# Sheet1.net
KiCad netlist of a schematic drawn in Altium Designer
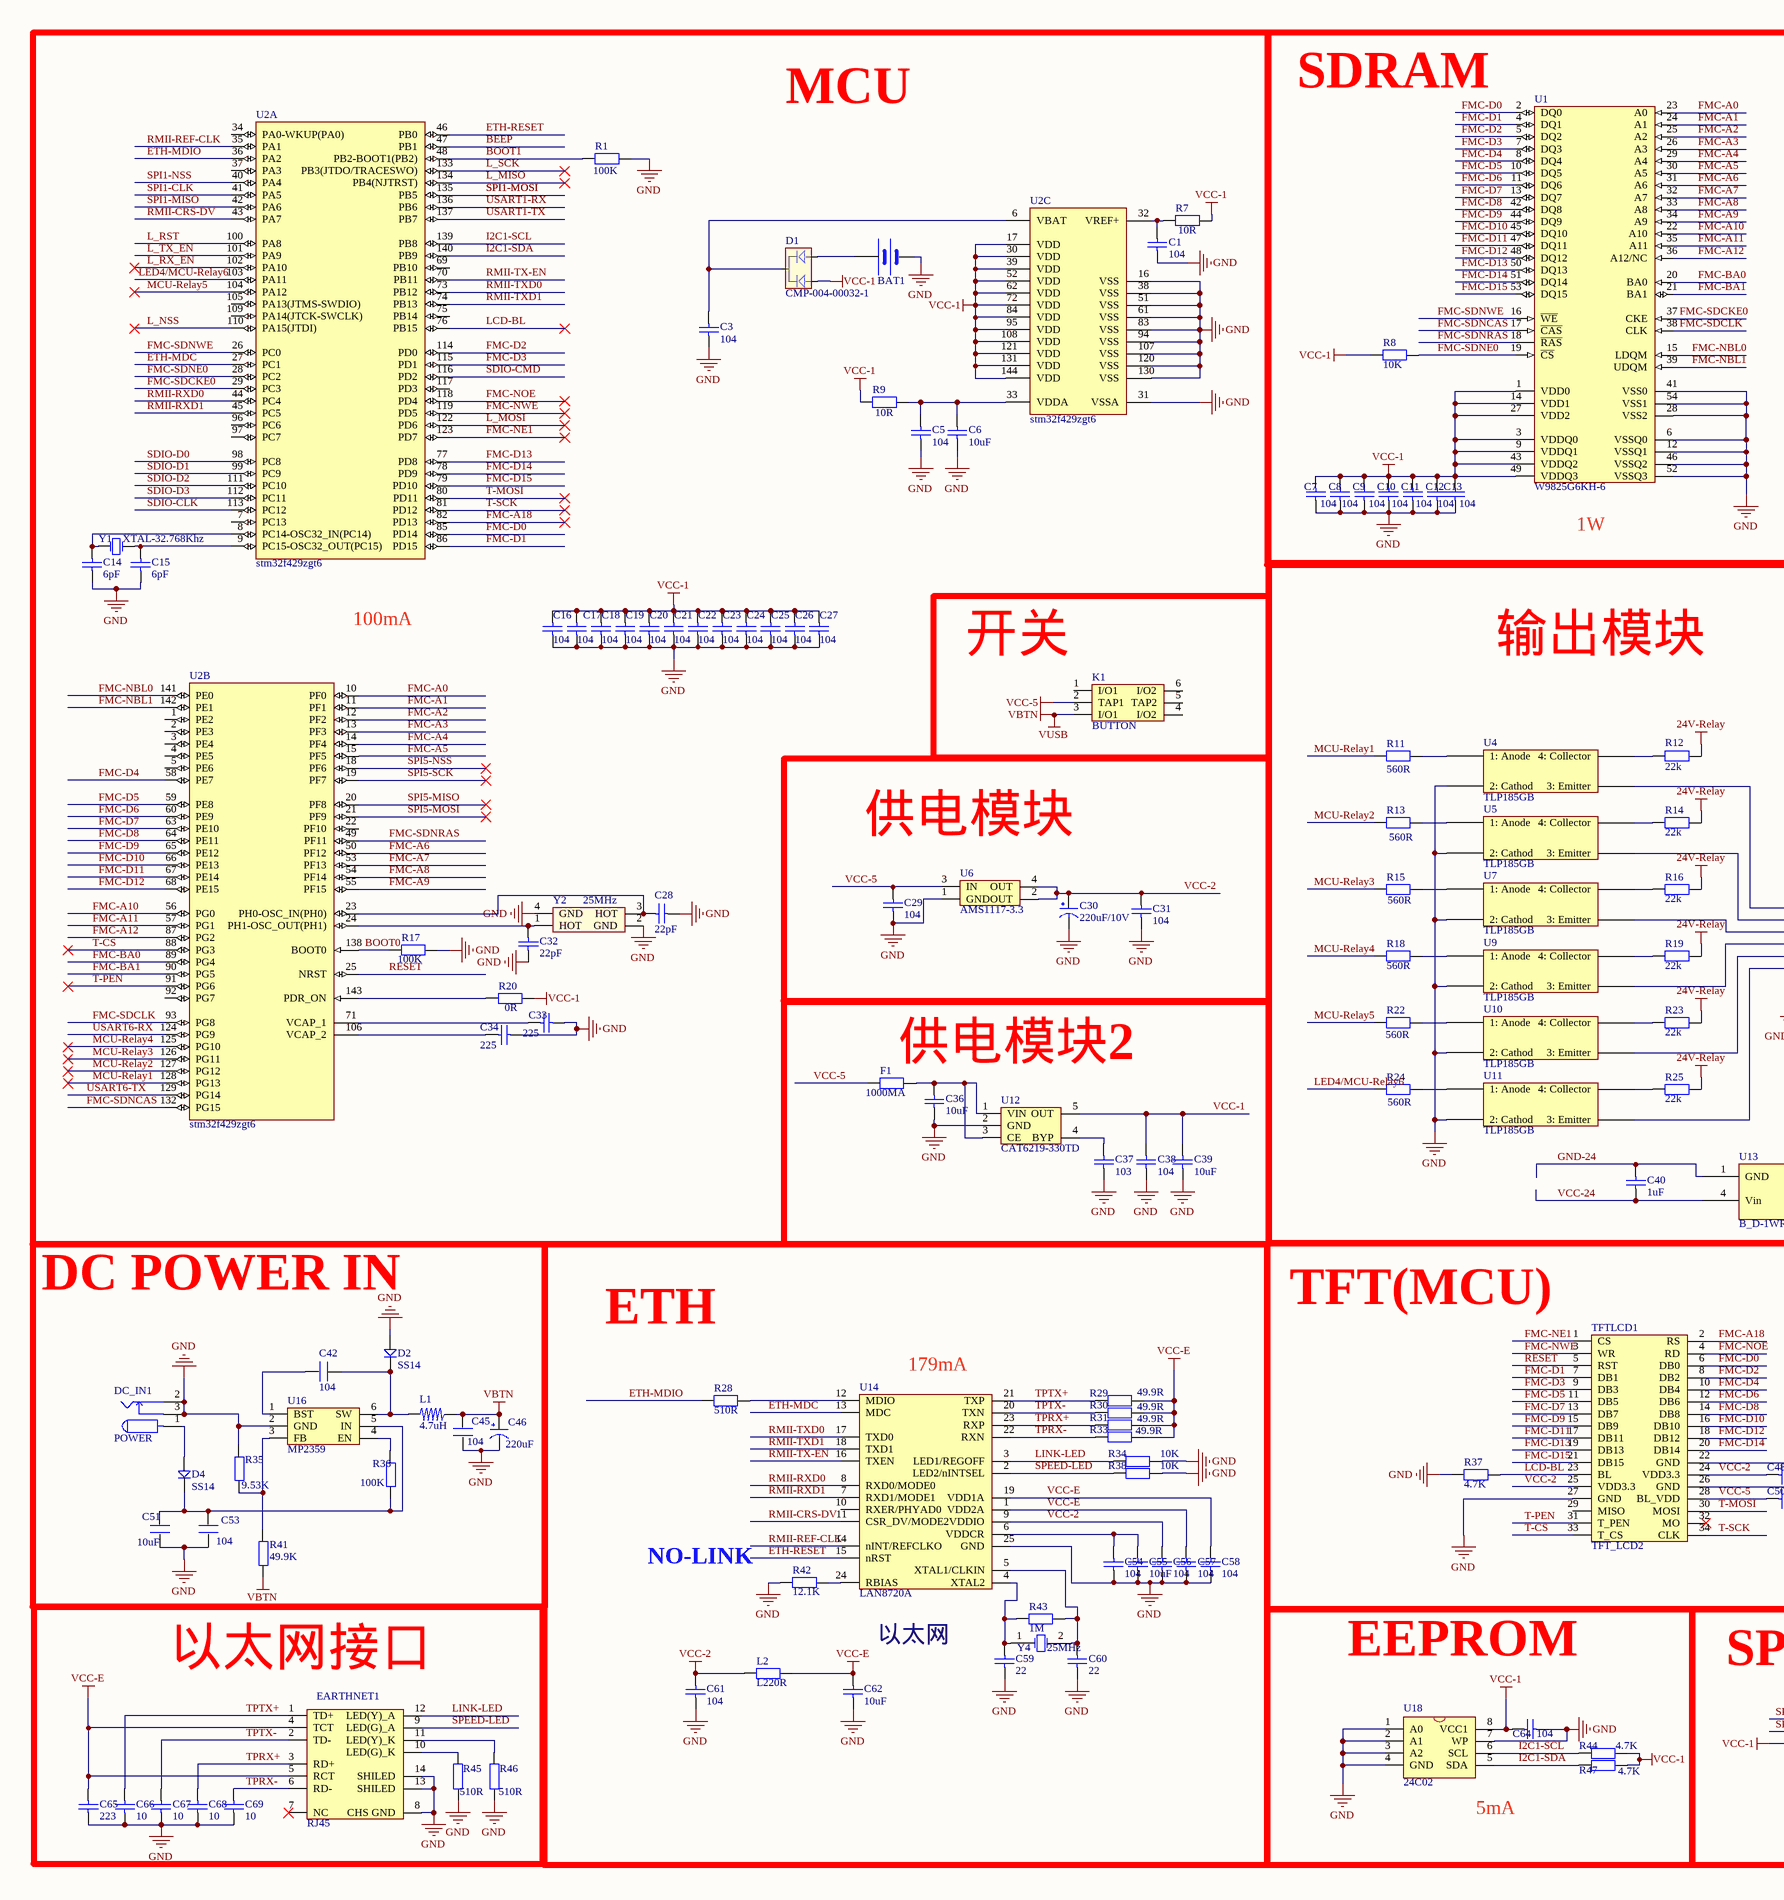
[diagram p0: Sheet1.SchDoc, left]
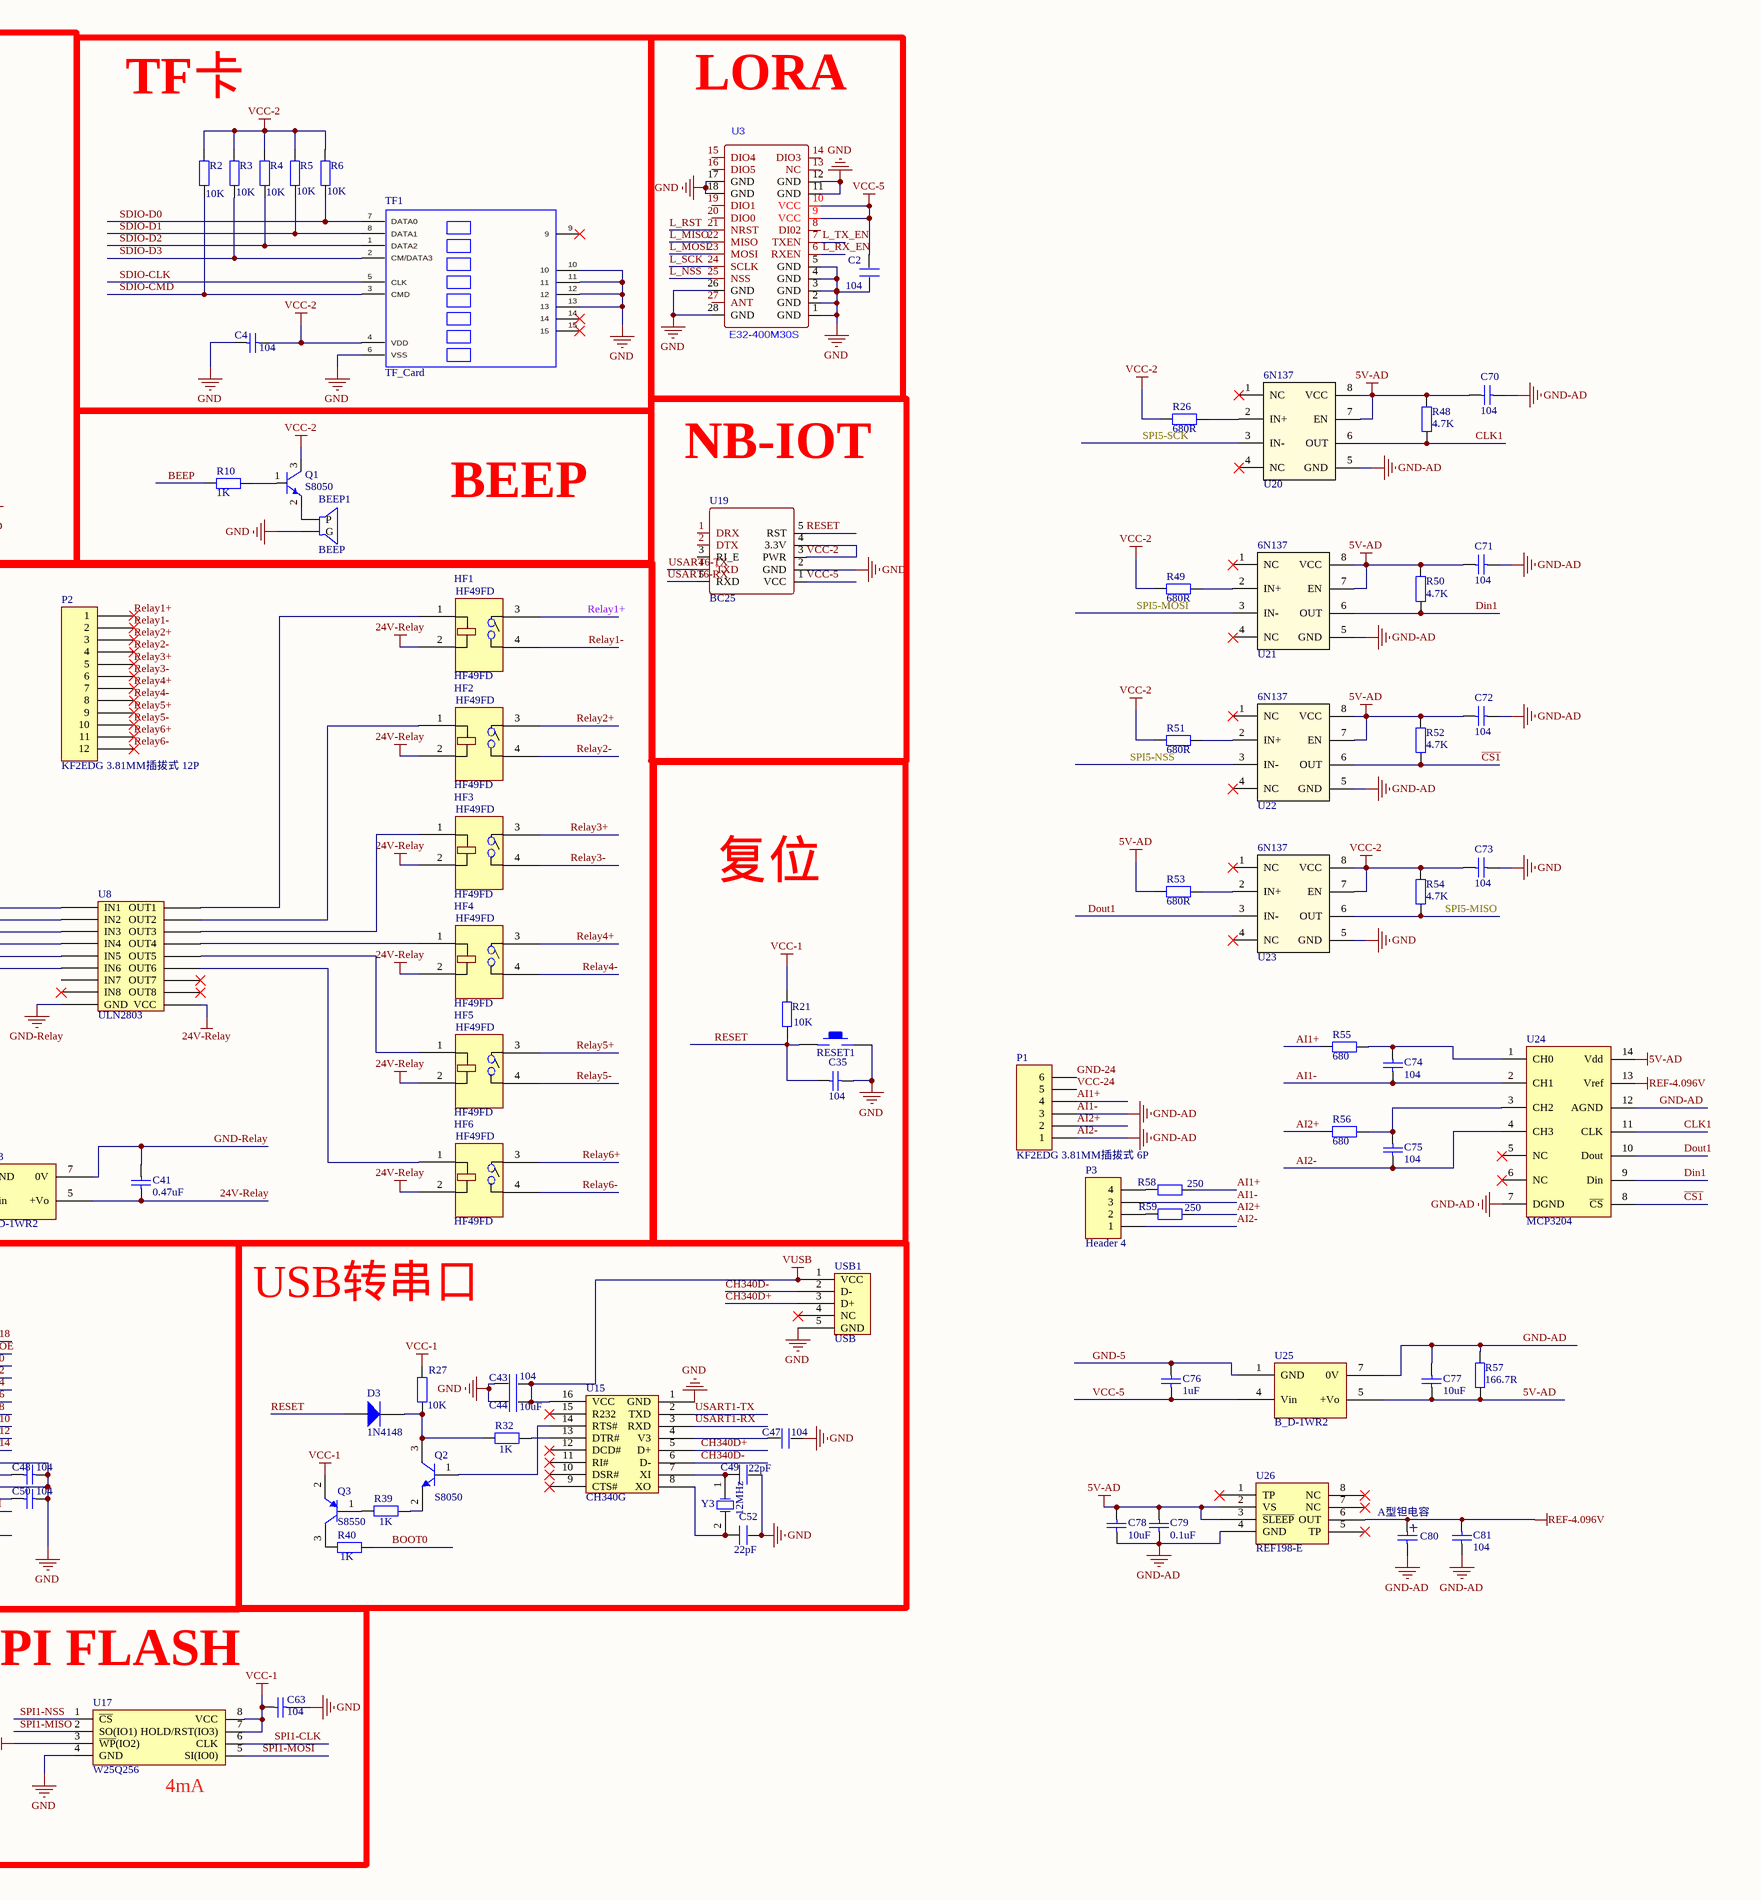
[diagram p1: Sheet1.SchDoc, right]

(export (version "E")
  (design (tool "Eeschema 10.0.6"))
  (components
    (comp (ref "BAT1")
      (value "CMP-00029-00001-1")
      (footprint "BATM")
      (libsource (lib "DigiPCBA Workspace") (part "BAT"))
    )
    (comp (ref "BEEP1")
      (value "BEEP")
      (footprint "BELL-5")
      (libsource (lib "DigiPCBA Workspace") (part "BEEP"))
    )
    (comp (ref "C1")
      (value "104")
      (footprint "LC-0603_C")
      (fields (field (name "Comment") "CAP"))
      (libsource (lib "DigiPCBA Workspace") (part "CAP"))
    )
    (comp (ref "C2") (value "104") (footprint "0603P") (libsource (lib "DigiPCBA Workspace") (part "C")))
    (comp (ref "C3")
      (value "104")
      (footprint "LC-0603_C")
      (fields (field (name "Comment") "CAP"))
      (libsource (lib "DigiPCBA Workspace") (part "CAP"))
    )
    (comp (ref "C4")
      (value "104")
      (footprint "CAP")
      (fields (field (name "Comment") "CMP-001-00083-1"))
      (libsource (lib "DigiPCBA Workspace") (part "CAP"))
    )
    (comp (ref "C5")
      (value "104")
      (footprint "LC-0603_C")
      (fields (field (name "Comment") "CAP"))
      (libsource (lib "DigiPCBA Workspace") (part "CAP"))
    )
    (comp (ref "C6")
      (value "10uF")
      (footprint "LC-0603_C")
      (fields (field (name "Comment") "CMP-001-00083-1"))
      (libsource (lib "DigiPCBA Workspace") (part "CAP"))
    )
    (comp (ref "C7")
      (value "104")
      (footprint "LC-0603_C")
      (fields (field (name "Comment") "CAP"))
      (libsource (lib "DigiPCBA Workspace") (part "CAP"))
    )
    (comp (ref "C8")
      (value "104")
      (footprint "LC-0603_C")
      (fields (field (name "Comment") "CAP"))
      (libsource (lib "DigiPCBA Workspace") (part "CAP"))
    )
    (comp (ref "C9")
      (value "104")
      (footprint "LC-0603_C")
      (fields (field (name "Comment") "CAP"))
      (libsource (lib "DigiPCBA Workspace") (part "CAP"))
    )
    (comp (ref "C10")
      (value "104")
      (footprint "LC-0603_C")
      (fields (field (name "Comment") "CAP"))
      (libsource (lib "DigiPCBA Workspace") (part "CAP"))
    )
    (comp (ref "C11")
      (value "104")
      (footprint "LC-0603_C")
      (fields (field (name "Comment") "CAP"))
      (libsource (lib "DigiPCBA Workspace") (part "CAP"))
    )
    (comp (ref "C12")
      (value "104")
      (footprint "LC-0603_C")
      (fields (field (name "Comment") "CAP"))
      (libsource (lib "DigiPCBA Workspace") (part "CAP"))
    )
    (comp (ref "C13")
      (value "104")
      (footprint "LC-0603_C")
      (fields (field (name "Comment") "CAP"))
      (libsource (lib "DigiPCBA Workspace") (part "CAP"))
    )
    (comp (ref "C14")
      (value "6pF")
      (footprint "LC-0603_C")
      (fields (field (name "Comment") "CMP-001-00083-1"))
      (libsource (lib "DigiPCBA Workspace") (part "CAP"))
    )
    (comp (ref "C15")
      (value "6pF")
      (footprint "LC-0603_C")
      (fields (field (name "Comment") "CMP-001-00083-1"))
      (libsource (lib "DigiPCBA Workspace") (part "CAP"))
    )
    (comp (ref "C16")
      (value "104")
      (footprint "LC-0603_C")
      (fields (field (name "Comment") "CMP-001-00083-1"))
      (libsource (lib "DigiPCBA Workspace") (part "CAP"))
    )
    (comp (ref "C17")
      (value "104")
      (footprint "LC-0603_C")
      (fields (field (name "Comment") "CMP-001-00083-1"))
      (libsource (lib "DigiPCBA Workspace") (part "CAP"))
    )
    (comp (ref "C18")
      (value "104")
      (footprint "LC-0603_C")
      (fields (field (name "Comment") "CAP"))
      (libsource (lib "DigiPCBA Workspace") (part "CAP"))
    )
    (comp (ref "C19")
      (value "104")
      (footprint "LC-0603_C")
      (fields (field (name "Comment") "CAP"))
      (libsource (lib "DigiPCBA Workspace") (part "CAP"))
    )
    (comp (ref "C20")
      (value "104")
      (footprint "LC-0603_C")
      (fields (field (name "Comment") "CAP"))
      (libsource (lib "DigiPCBA Workspace") (part "CAP"))
    )
    (comp (ref "C21")
      (value "104")
      (footprint "LC-0603_C")
      (fields (field (name "Comment") "CAP"))
      (libsource (lib "DigiPCBA Workspace") (part "CAP"))
    )
    (comp (ref "C22")
      (value "104")
      (footprint "LC-0603_C")
      (fields (field (name "Comment") "CAP"))
      (libsource (lib "DigiPCBA Workspace") (part "CAP"))
    )
    (comp (ref "C23")
      (value "104")
      (footprint "LC-0603_C")
      (fields (field (name "Comment") "CAP"))
      (libsource (lib "DigiPCBA Workspace") (part "CMP-001-00083-1"))
    )
    (comp (ref "C24")
      (value "104")
      (footprint "LC-0603_C")
      (libsource (lib "DigiPCBA Workspace") (part "CAP"))
    )
    (comp (ref "C25")
      (value "104")
      (footprint "LC-0603_C")
      (fields (field (name "Comment") "CAP"))
      (libsource (lib "DigiPCBA Workspace") (part "CAP"))
    )
    (comp (ref "C26")
      (value "104")
      (footprint "LC-0603_C")
      (fields (field (name "Comment") "CAP"))
      (libsource (lib "DigiPCBA Workspace") (part "CAP"))
    )
    (comp (ref "C27")
      (value "104")
      (footprint "LC-0603_C")
      (fields (field (name "Comment") "CAP"))
      (libsource (lib "DigiPCBA Workspace") (part "CAP"))
    )
    (comp (ref "C28")
      (value "22pF")
      (footprint "LC-0603_C")
      (fields (field (name "Comment") "CMP-001-00083-1"))
      (libsource (lib "DigiPCBA Workspace") (part "CAP"))
    )
    (comp (ref "C29")
      (value "104")
      (footprint "CAP")
      (fields (field (name "Comment") "CMP-001-00083-1"))
      (libsource (lib "DigiPCBA Workspace") (part "CAP"))
    )
    (comp (ref "C30")
      (value "220uF/10V")
      (footprint "220uF/10V")
      (libsource (lib "DigiPCBA Workspace") (part "CAP贴片电解电容"))
    )
    (comp (ref "C31")
      (value "104")
      (footprint "CAP")
      (fields (field (name "Comment") "CMP-001-00083-1"))
      (libsource (lib "DigiPCBA Workspace") (part "CAP"))
    )
    (comp (ref "C32")
      (value "22pF")
      (footprint "LC-0603_C")
      (fields (field (name "Comment") "CMP-001-00083-1"))
      (libsource (lib "DigiPCBA Workspace") (part "CAP"))
    )
    (comp (ref "C33")
      (value "225")
      (footprint "LC-0603_C")
      (fields (field (name "Comment") "CMP-001-00083-1"))
      (libsource (lib "DigiPCBA Workspace") (part "CAP"))
    )
    (comp (ref "C34")
      (value "225")
      (footprint "LC-0603_C")
      (fields (field (name "Comment") "CMP-001-00083-1"))
      (libsource (lib "DigiPCBA Workspace") (part "CAP"))
    )
    (comp (ref "C35")
      (value "104")
      (footprint "LC-0603_C")
      (fields (field (name "Comment") "CAP"))
      (libsource (lib "DigiPCBA Workspace") (part "CAP"))
    )
    (comp (ref "C36")
      (value "10uF")
      (footprint "LC-0603_C")
      (fields (field (name "Comment") "CMP-001-00083-1"))
      (libsource (lib "DigiPCBA Workspace") (part "CAP"))
    )
    (comp (ref "C37")
      (value "103")
      (footprint "CAP")
      (fields (field (name "Comment") "CMP-001-00083-1"))
      (libsource (lib "DigiPCBA Workspace") (part "CAP"))
    )
    (comp (ref "C38")
      (value "104")
      (footprint "CAP")
      (fields (field (name "Comment") "CMP-001-00083-1"))
      (libsource (lib "DigiPCBA Workspace") (part "CAP"))
    )
    (comp (ref "C39")
      (value "10uF")
      (footprint "LC-0603_C")
      (fields (field (name "Comment") "CMP-001-00083-1"))
      (libsource (lib "DigiPCBA Workspace") (part "CAP"))
    )
    (comp (ref "C40")
      (value "1uF")
      (footprint "CAP")
      (fields (field (name "Comment") "CMP-001-00083-1"))
      (libsource (lib "DigiPCBA Workspace") (part "CAP"))
    )
    (comp (ref "C41")
      (value "0.47uF")
      (footprint "CAP")
      (fields (field (name "Comment") "CMP-001-00083-1"))
      (libsource (lib "DigiPCBA Workspace") (part "CAP"))
    )
    (comp (ref "C42") (value "104") (footprint "0603P") (libsource (lib "DigiPCBA Workspace") (part "C")))
    (comp (ref "C43") (value "104") (footprint "0603P") (libsource (lib "DigiPCBA Workspace") (part "C")))
    (comp (ref "C44") (value "10uF") (footprint "0603P") (libsource (lib "DigiPCBA Workspace") (part "C")))
    (comp (ref "C45") (value "104") (footprint "0603P") (libsource (lib "DigiPCBA Workspace") (part "C")))
    (comp (ref "C46") (value "220uF") (footprint "CC6.56.5") (libsource (lib "") (part "CAP_1")))
    (comp (ref "C47") (value "104") (footprint "0603P") (libsource (lib "DigiPCBA Workspace") (part "C")))
    (comp (ref "C48")
      (value "104")
      (footprint "CAP")
      (fields (field (name "Comment") "CMP-001-00083-1"))
      (libsource (lib "DigiPCBA Workspace") (part "CAP"))
    )
    (comp (ref "C49") (value "22pF") (footprint "0603P") (libsource (lib "DigiPCBA Workspace") (part "C")))
    (comp (ref "C50")
      (value "104")
      (footprint "CAP")
      (fields (field (name "Comment") "CMP-001-00083-1"))
      (libsource (lib "DigiPCBA Workspace") (part "CAP"))
    )
    (comp (ref "C51") (value "10uF") (footprint "0603P") (libsource (lib "DigiPCBA Workspace") (part "C")))
    (comp (ref "C52") (value "22pF") (footprint "0603P") (libsource (lib "DigiPCBA Workspace") (part "C")))
    (comp (ref "C53") (value "104") (footprint "0603P") (libsource (lib "DigiPCBA Workspace") (part "C")))
    (comp (ref "C54")
      (value "104")
      (footprint "LC-0603_C")
      (fields (field (name "Comment") "CAP"))
      (libsource (lib "DigiPCBA Workspace") (part "CAP"))
    )
    (comp (ref "C55")
      (value "10uF")
      (footprint "LC-0603_C")
      (fields (field (name "Comment") "CMP-001-00083-1"))
      (libsource (lib "DigiPCBA Workspace") (part "CAP"))
    )
    (comp (ref "C56")
      (value "104")
      (footprint "LC-0603_C")
      (fields (field (name "Comment") "CAP"))
      (libsource (lib "DigiPCBA Workspace") (part "CAP"))
    )
    (comp (ref "C57")
      (value "104")
      (footprint "LC-0603_C")
      (fields (field (name "Comment") "CAP"))
      (libsource (lib "DigiPCBA Workspace") (part "CAP"))
    )
    (comp (ref "C58")
      (value "104")
      (footprint "LC-0603_C")
      (fields (field (name "Comment") "CAP"))
      (libsource (lib "DigiPCBA Workspace") (part "CAP"))
    )
    (comp (ref "C59")
      (value "22")
      (footprint "LC-0603_C")
      (fields (field (name "Comment") "CMP-001-00083-1"))
      (libsource (lib "DigiPCBA Workspace") (part "CAP"))
    )
    (comp (ref "C60")
      (value "22")
      (footprint "LC-0603_C")
      (fields (field (name "Comment") "CMP-001-00083-1"))
      (libsource (lib "DigiPCBA Workspace") (part "CAP"))
    )
    (comp (ref "C61")
      (value "104")
      (footprint "CAP")
      (fields (field (name "Comment") "CMP-001-00083-1"))
      (libsource (lib "DigiPCBA Workspace") (part "CAP"))
    )
    (comp (ref "C62")
      (value "10uF")
      (footprint "LC-0603_C")
      (fields (field (name "Comment") "CMP-001-00083-1"))
      (libsource (lib "DigiPCBA Workspace") (part "CAP"))
    )
    (comp (ref "C63")
      (value "104")
      (footprint "CAP")
      (fields (field (name "Comment") "CMP-001-00083-1"))
      (libsource (lib "DigiPCBA Workspace") (part "CAP"))
    )
    (comp (ref "C64")
      (value "104")
      (footprint "CAP")
      (fields (field (name "Comment") "CMP-001-00083-1"))
      (libsource (lib "DigiPCBA Workspace") (part "CAP"))
    )
    (comp (ref "C65")
      (value "223")
      (footprint "CAP")
      (fields (field (name "Comment") "CMP-001-00083-1"))
      (libsource (lib "DigiPCBA Workspace") (part "CAP"))
    )
    (comp (ref "C66")
      (value "10")
      (footprint "CAP")
      (fields (field (name "Comment") "CMP-001-00083-1"))
      (libsource (lib "DigiPCBA Workspace") (part "CAP"))
    )
    (comp (ref "C67")
      (value "10")
      (footprint "CAP")
      (fields (field (name "Comment") "CMP-001-00083-1"))
      (libsource (lib "DigiPCBA Workspace") (part "CAP"))
    )
    (comp (ref "C68")
      (value "10")
      (footprint "CAP")
      (fields (field (name "Comment") "CMP-001-00083-1"))
      (libsource (lib "DigiPCBA Workspace") (part "CAP"))
    )
    (comp (ref "C69")
      (value "10")
      (footprint "CAP")
      (fields (field (name "Comment") "CMP-001-00083-1"))
      (libsource (lib "DigiPCBA Workspace") (part "CAP"))
    )
    (comp (ref "C70")
      (value "104")
      (footprint "CAP")
      (fields (field (name "Comment") "CAP"))
      (libsource (lib "Integrated_Library3") (part "CAP"))
    )
    (comp (ref "C71")
      (value "104")
      (footprint "CAP")
      (fields (field (name "Comment") "CAP"))
      (libsource (lib "Integrated_Library3") (part "CAP"))
    )
    (comp (ref "C72")
      (value "104")
      (footprint "CAP")
      (fields (field (name "Comment") "CAP"))
      (libsource (lib "Integrated_Library3") (part "CAP"))
    )
    (comp (ref "C73")
      (value "104")
      (footprint "CAP")
      (fields (field (name "Comment") "CAP"))
      (libsource (lib "Integrated_Library3") (part "CAP"))
    )
    (comp (ref "C74")
      (value "104")
      (footprint "CAP")
      (fields (field (name "Comment") "CAP"))
      (libsource (lib "Integrated_Library3") (part "CAP"))
    )
    (comp (ref "C75")
      (value "104")
      (footprint "CAP")
      (fields (field (name "Comment") "CAP"))
      (libsource (lib "Integrated_Library3") (part "CAP"))
    )
    (comp (ref "C76")
      (value "1uF")
      (footprint "CAP")
      (fields (field (name "Comment") "CMP-001-00083-1"))
      (libsource (lib "DigiPCBA Workspace") (part "CAP"))
    )
    (comp (ref "C77")
      (value "10uF")
      (footprint "CAP")
      (fields (field (name "Comment") "CMP-001-00083-1"))
      (libsource (lib "DigiPCBA Workspace") (part "CAP"))
    )
    (comp (ref "C78")
      (value "10uF")
      (footprint "CAP")
      (fields (field (name "Comment") "CAP"))
      (libsource (lib "Integrated_Library3") (part "CAP"))
    )
    (comp (ref "C79")
      (value "0.1uF")
      (footprint "CAP")
      (fields (field (name "Comment") "CAP"))
      (libsource (lib "Integrated_Library3") (part "CAP"))
    )
    (comp (ref "C80")
      (value "A型钽电容")
      (footprint "A型贴片钽电容")
      (libsource (lib "DigiPCBA Workspace") (part "A型钽电容"))
    )
    (comp (ref "C81")
      (value "104")
      (footprint "CAP")
      (fields (field (name "Comment") "CAP"))
      (libsource (lib "Integrated_Library3") (part "CAP"))
    )
    (comp (ref "D1")
      (value "CMP-004-00032-1")
      (footprint "SOT-23")
      (description "双肖特基二极管")
      (libsource (lib "DigiPCBA Workspace") (part "BAT54C"))
    )
    (comp (ref "D2")
      (value "SS14")
      (footprint "DIODE_3*5.3")
      (libsource (lib "DigiPCBA Workspace") (part "D"))
    )
    (comp (ref "D3")
      (value "1N4148")
      (footprint "3.2X1.6X1.1")
      (fields (field (name "SOURCE") "主控芯片.SCHLIB"))
      (libsource (lib "DigiPCBA Workspace") (part "DIODE"))
    )
    (comp (ref "D4")
      (value "SS14")
      (footprint "DIODE_3*5.3")
      (libsource (lib "DigiPCBA Workspace") (part "D"))
    )
    (comp (ref "DC_IN1")
      (value "POWER")
      (footprint "DC10B")
      (libsource (lib "DigiPCBA Workspace") (part "POW"))
    )
    (comp (ref "EARTHNET1")
      (value "RJ45")
      (footprint "HR911105A")
      (libsource (lib "DigiPCBA Workspace") (part "HR911105"))
    )
    (comp (ref "F1")
      (value "1000MA")
      (footprint "RES")
      (fields (field (name "Comment") "CMP-009-00177-1"))
      (libsource (lib "") (part "RES_2"))
    )
    (comp (ref "HF1")
      (value "HF49FD")
      (footprint "HF49FDXXX_1HX1")
      (fields (field (name "SOURCE") "电源模块.SCHLIB"))
      (libsource (lib "DigiPCBA Workspace") (part "HF49FD"))
    )
    (comp (ref "HF2")
      (value "HF49FD")
      (footprint "HF49FDXXX_1HX1")
      (fields (field (name "SOURCE") "电源模块.SCHLIB"))
      (libsource (lib "DigiPCBA Workspace") (part "HF49FD"))
    )
    (comp (ref "HF3")
      (value "HF49FD")
      (footprint "HF49FDXXX_1HX1")
      (fields (field (name "SOURCE") "电源模块.SCHLIB"))
      (libsource (lib "DigiPCBA Workspace") (part "HF49FD"))
    )
    (comp (ref "HF4")
      (value "HF49FD")
      (footprint "HF49FDXXX_1HX1")
      (fields (field (name "SOURCE") "电源模块.SCHLIB"))
      (libsource (lib "DigiPCBA Workspace") (part "HF49FD"))
    )
    (comp (ref "HF5")
      (value "HF49FD")
      (footprint "HF49FDXXX_1HX1")
      (fields (field (name "SOURCE") "电源模块.SCHLIB"))
      (libsource (lib "DigiPCBA Workspace") (part "HF49FD"))
    )
    (comp (ref "HF6")
      (value "HF49FD")
      (footprint "HF49FDXXX_1HX1")
      (fields (field (name "SOURCE") "电源模块.SCHLIB"))
      (libsource (lib "DigiPCBA Workspace") (part "HF49FD"))
    )
    (comp (ref "K1")
      (value "BUTTON")
      (footprint "BTN8.5*8.5")
      (libsource (lib "DigiPCBA Workspace") (part "BUTTON"))
    )
    (comp (ref "L1")
      (value "4.7uH")
      (footprint "L_SOP74")
      (libsource (lib "DigiPCBA Workspace") (part "L_SOP"))
    )
    (comp (ref "L2") (value "L220R") (footprint "RES") (libsource (lib "") (part "RES_2")))
    (comp (ref "P1")
      (value "KF2EDG 3.81MM插拔式 6P")
      (footprint "KF2EDG 3.81MM拔插")
      (description "Header, 6-Pin")
      (fields (field (name "PUBLISHER") "Altium Limited"))
      (libsource (lib "电源模块") (part "Header 6"))
    )
    (comp (ref "P2")
      (value "KF2EDG 3.81MM插拔式 12P")
      (footprint "KF2EDG 3.81mm插拔式")
      (fields (field (name "SOURCE") "电源模块.SCHLIB"))
      (libsource (lib "DigiPCBA Workspace") (part "KF2EDG 3.81MM插拔式 12P"))
    )
    (comp (ref "P3")
      (value "Header 4")
      (footprint "HDR1X4")
      (description "Header, 4-Pin")
      (fields (field (name "PUBLISHER") "Altium Limited"))
      (libsource (lib "DigiPCBA Workspace") (part "Header 4"))
    )
    (comp (ref "Q1")
      (value "S8050")
      (footprint "NPN/PNP")
      (description "NPN")
      (libsource (lib "DigiPCBA Workspace") (part "NPN"))
    )
    (comp (ref "Q2")
      (value "S8050")
      (footprint "SOT-23_N")
      (fields (field (name "SOURCE") "主控芯片.SCHLIB"))
      (libsource (lib "DigiPCBA Workspace") (part "QNPN"))
    )
    (comp (ref "Q3")
      (value "S8550")
      (footprint "SOT-23B_N")
      (fields (field (name "SOURCE") "主控芯片.SCHLIB"))
      (libsource (lib "DigiPCBA Workspace") (part "QPNP"))
    )
    (comp (ref "R1")
      (value "100K")
      (footprint "LC-0603_R")
      (fields (field (name "Comment") "CMP-009-00177-1"))
      (libsource (lib "DigiPCBA Workspace") (part "RES"))
    )
    (comp (ref "R2") (value "10K") (footprint "RES") (libsource (lib "") (part "RES_1")))
    (comp (ref "R3") (value "10K") (footprint "RES") (libsource (lib "") (part "RES_1")))
    (comp (ref "R4") (value "10K") (footprint "RES") (libsource (lib "") (part "RES_1")))
    (comp (ref "R5") (value "10K") (footprint "RES") (libsource (lib "") (part "RES_1")))
    (comp (ref "R6") (value "10K") (footprint "RES") (libsource (lib "") (part "RES_1")))
    (comp (ref "R7")
      (value "10R")
      (footprint "LC-0603_R")
      (fields (field (name "Comment") "CMP-009-00177-1"))
      (libsource (lib "") (part "RES_2"))
    )
    (comp (ref "R8") (value "10K") (footprint "LC-0603_R") (libsource (lib "") (part "RES_2")))
    (comp (ref "R9")
      (value "10R")
      (footprint "LC-0603_R")
      (fields (field (name "Comment") "CMP-009-00177-1"))
      (libsource (lib "") (part "RES_2"))
    )
    (comp (ref "R10") (value "1K") (footprint "RES") (libsource (lib "") (part "RES_2")))
    (comp (ref "R11")
      (value "560R")
      (footprint "RES")
      (fields (field (name "Comment") "RES") (field (name "SOURCE") "电源模块.SCHLIB"))
      (libsource (lib "DigiPCBA Workspace") (part "RES_1"))
    )
    (comp (ref "R12")
      (value "22k")
      (footprint "RES")
      (fields (field (name "Comment") "CMP-009-00180-1") (field (name "SOURCE") "电源模块.SCHLIB"))
      (libsource (lib "DigiPCBA Workspace") (part "RES_1"))
    )
    (comp (ref "R13")
      (value "560R")
      (footprint "RES")
      (fields (field (name "Comment") "RES") (field (name "SOURCE") "电源模块.SCHLIB"))
      (libsource (lib "DigiPCBA Workspace") (part "RES_1"))
    )
    (comp (ref "R14")
      (value "22k")
      (footprint "RES")
      (fields (field (name "Comment") "CMP-009-00180-1") (field (name "SOURCE") "电源模块.SCHLIB"))
      (libsource (lib "DigiPCBA Workspace") (part "RES_1"))
    )
    (comp (ref "R15")
      (value "560R")
      (footprint "RES")
      (fields (field (name "Comment") "RES") (field (name "SOURCE") "电源模块.SCHLIB"))
      (libsource (lib "DigiPCBA Workspace") (part "RES_1"))
    )
    (comp (ref "R16")
      (value "22k")
      (footprint "RES")
      (fields (field (name "Comment") "CMP-009-00180-1") (field (name "SOURCE") "电源模块.SCHLIB"))
      (libsource (lib "DigiPCBA Workspace") (part "RES_1"))
    )
    (comp (ref "R17")
      (value "100K")
      (footprint "LC-0603_R")
      (fields (field (name "Comment") "CMP-009-00177-1"))
      (libsource (lib "") (part "RES_2"))
    )
    (comp (ref "R18")
      (value "560R")
      (footprint "RES")
      (fields (field (name "Comment") "RES") (field (name "SOURCE") "电源模块.SCHLIB"))
      (libsource (lib "DigiPCBA Workspace") (part "RES_1"))
    )
    (comp (ref "R19")
      (value "22k")
      (footprint "RES")
      (fields (field (name "Comment") "CMP-009-00180-1") (field (name "SOURCE") "电源模块.SCHLIB"))
      (libsource (lib "DigiPCBA Workspace") (part "RES_1"))
    )
    (comp (ref "R20")
      (value "0R")
      (footprint "RES")
      (fields (field (name "Comment") "CMP-009-00177-1"))
      (libsource (lib "DigiPCBA Workspace") (part "RES"))
    )
    (comp (ref "R21") (value "10K") (footprint "LC-0603_R") (libsource (lib "") (part "RES_1")))
    (comp (ref "R22")
      (value "560R")
      (footprint "RES")
      (fields (field (name "Comment") "RES") (field (name "SOURCE") "电源模块.SCHLIB"))
      (libsource (lib "DigiPCBA Workspace") (part "RES_1"))
    )
    (comp (ref "R23")
      (value "22k")
      (footprint "RES")
      (fields (field (name "Comment") "CMP-009-00180-1") (field (name "SOURCE") "电源模块.SCHLIB"))
      (libsource (lib "DigiPCBA Workspace") (part "RES_1"))
    )
    (comp (ref "R24")
      (value "560R")
      (footprint "RES")
      (fields (field (name "Comment") "RES") (field (name "SOURCE") "电源模块.SCHLIB"))
      (libsource (lib "DigiPCBA Workspace") (part "RES_1"))
    )
    (comp (ref "R25")
      (value "22k")
      (footprint "RES")
      (fields (field (name "Comment") "CMP-009-00180-1") (field (name "SOURCE") "电源模块.SCHLIB"))
      (libsource (lib "DigiPCBA Workspace") (part "RES_1"))
    )
    (comp (ref "R26")
      (value "680R")
      (footprint "RES")
      (fields (field (name "Comment") "RES"))
      (libsource (lib "") (part "RES_1"))
    )
    (comp (ref "R27")
      (value "10K")
      (footprint "0805R")
      (fields (field (name "SOURCE") "主控芯片.SCHLIB"))
      (libsource (lib "") (part "RES_4"))
    )
    (comp (ref "R28") (value "510R") (footprint "LC-0603_R") (libsource (lib "") (part "RES_2")))
    (comp (ref "R29") (value "49.9R") (footprint "LC-0603_R") (libsource (lib "") (part "RES_2")))
    (comp (ref "R30") (value "49.9R") (footprint "LC-0603_R") (libsource (lib "") (part "RES_2")))
    (comp (ref "R31") (value "49.9R") (footprint "LC-0603_R") (libsource (lib "") (part "RES_2")))
    (comp (ref "R32")
      (value "1K")
      (footprint "0805R")
      (fields (field (name "SOURCE") "主控芯片.SCHLIB"))
      (libsource (lib "") (part "RES_3"))
    )
    (comp (ref "R33") (value "49.9R") (footprint "LC-0603_R") (libsource (lib "") (part "RES_2")))
    (comp (ref "R34") (value "10K") (footprint "LC-0603_R") (libsource (lib "") (part "RES_2")))
    (comp (ref "R35") (value "9.53K") (footprint "0603P") (libsource (lib "DigiPCBA Workspace") (part "R")))
    (comp (ref "R36") (value "100K") (footprint "0603P") (libsource (lib "DigiPCBA Workspace") (part "R")))
    (comp (ref "R37")
      (value "4.7K")
      (footprint "RES")
      (fields (field (name "Comment") "CMP-009-00180-1") (field (name "SOURCE") "电源模块.SCHLIB"))
      (libsource (lib "DigiPCBA Workspace") (part "RES_1"))
    )
    (comp (ref "R38") (value "10K") (footprint "LC-0603_R") (libsource (lib "") (part "RES_2")))
    (comp (ref "R39")
      (value "1K")
      (footprint "0805R")
      (fields (field (name "SOURCE") "主控芯片.SCHLIB"))
      (libsource (lib "") (part "RES_3"))
    )
    (comp (ref "R40")
      (value "1K")
      (footprint "0805R")
      (fields (field (name "SOURCE") "主控芯片.SCHLIB"))
      (libsource (lib "") (part "RES_5"))
    )
    (comp (ref "R41") (value "49.9K") (footprint "0603P") (libsource (lib "DigiPCBA Workspace") (part "R")))
    (comp (ref "R42") (value "12.1K") (footprint "LC-0603_R") (libsource (lib "") (part "RES_2")))
    (comp (ref "R43") (value "1M") (footprint "LC-0603_R") (libsource (lib "") (part "RES_2")))
    (comp (ref "R44")
      (value "4.7K")
      (footprint "RES")
      (fields (field (name "Comment") "CMP-009-00180-1") (field (name "SOURCE") "电源模块.SCHLIB"))
      (libsource (lib "DigiPCBA Workspace") (part "RES_1"))
    )
    (comp (ref "R45") (value "510R") (footprint "RES") (libsource (lib "") (part "RES_1")))
    (comp (ref "R46") (value "510R") (footprint "RES") (libsource (lib "") (part "RES_1")))
    (comp (ref "R47") (value "4.7K") (footprint "RES") (libsource (lib "") (part "RES_2")))
    (comp (ref "R48")
      (value "4.7K")
      (footprint "RES")
      (fields (field (name "Comment") "RES"))
      (libsource (lib "Integrated_Library3") (part "RES"))
    )
    (comp (ref "R49")
      (value "680R")
      (footprint "RES")
      (fields (field (name "Comment") "RES"))
      (libsource (lib "") (part "RES_1"))
    )
    (comp (ref "R50")
      (value "4.7K")
      (footprint "RES")
      (fields (field (name "Comment") "RES"))
      (libsource (lib "Integrated_Library3") (part "RES"))
    )
    (comp (ref "R51")
      (value "680R")
      (footprint "RES")
      (fields (field (name "Comment") "RES"))
      (libsource (lib "") (part "RES_1"))
    )
    (comp (ref "R52")
      (value "4.7K")
      (footprint "RES")
      (fields (field (name "Comment") "RES"))
      (libsource (lib "Integrated_Library3") (part "RES"))
    )
    (comp (ref "R53")
      (value "680R")
      (footprint "RES")
      (fields (field (name "Comment") "RES"))
      (libsource (lib "") (part "RES_1"))
    )
    (comp (ref "R54")
      (value "4.7K")
      (footprint "RES")
      (fields (field (name "Comment") "RES"))
      (libsource (lib "Integrated_Library3") (part "RES"))
    )
    (comp (ref "R55")
      (value "680")
      (footprint "RES")
      (fields (field (name "Comment") "RES"))
      (libsource (lib "") (part "RES_1"))
    )
    (comp (ref "R56")
      (value "680")
      (footprint "RES")
      (fields (field (name "Comment") "RES"))
      (libsource (lib "") (part "RES_1"))
    )
    (comp (ref "R57")
      (value "166.7R")
      (footprint "1206_R")
      (fields (field (name "Comment") "CMP-009-00180-1") (field (name "SOURCE") "电源模块.SCHLIB"))
      (libsource (lib "") (part "RES_1_1"))
    )
    (comp (ref "R58")
      (value "250")
      (footprint "1206_R")
      (fields (field (name "Comment") "CMP-009-00180-1") (field (name "SOURCE") "电源模块.SCHLIB"))
      (libsource (lib "") (part "RES_1_2"))
    )
    (comp (ref "R59")
      (value "250")
      (footprint "1206_R")
      (fields (field (name "Comment") "CMP-009-00180-1") (field (name "SOURCE") "电源模块.SCHLIB"))
      (libsource (lib "") (part "RES_1_2"))
    )
    (comp (ref "RESET1")
      (value "CMP-012-000013-1")
      (footprint "KEY_M")
      (libsource (lib "DigiPCBA Workspace") (part "KEY_M"))
    )
    (comp (ref "TF1")
      (value "TF_Card")
      (footprint "TF_CARD")
      (libsource (lib "DigiPCBA Workspace") (part "TF_Card"))
    )
    (comp (ref "TFTLCD1")
      (value "TFT_LCD2")
      (footprint "DB2*17-3.5")
      (fields (field (name "SOURCE") "显示模块.SCHLIB"))
      (libsource (lib "DigiPCBA Workspace") (part "TFT_LCD2"))
    )
    (comp (ref "U1")
      (value "W9825G6KH-6")
      (footprint "TSOP54")
      (description "32MB SDRAM")
      (libsource (lib "DigiPCBA Workspace") (part "IS42S16160B"))
    )
    (comp (ref "U2")
      (value "stm32f429zgt6")
      (footprint "STM-LQFP144_N")
      (fields (field (name "MANUFACTURER") "STMicroelectronics") (field (name "PARTNUMBER") "STM32F429ZGT6"))
      (libsource (lib "DigiPCBA Workspace") (part "STM32F429ZGT6"))
    )
    (comp (ref "U3")
      (value "E32-400M30S")
      (footprint "WIRELM-SMD_E32-400M30S")
      (libsource (lib "DigiPCBA Workspace") (part "E32-400M30S"))
    )
    (comp (ref "U4")
      (value "TLP185GB")
      (footprint "TLP185GB")
      (fields (field (name "SOURCE") "电源模块.SCHLIB"))
      (libsource (lib "DigiPCBA Workspace") (part "TLP185GB"))
    )
    (comp (ref "U5")
      (value "TLP185GB")
      (footprint "TLP185GB")
      (fields (field (name "SOURCE") "电源模块.SCHLIB"))
      (libsource (lib "DigiPCBA Workspace") (part "TLP185GB"))
    )
    (comp (ref "U6")
      (value "AMS1117-3.3")
      (footprint "AMS1117")
      (libsource (lib "DigiPCBA Workspace") (part "AMS1117"))
    )
    (comp (ref "U7")
      (value "TLP185GB")
      (footprint "TLP185GB")
      (fields (field (name "SOURCE") "电源模块.SCHLIB"))
      (libsource (lib "DigiPCBA Workspace") (part "TLP185GB"))
    )
    (comp (ref "U8")
      (value "ULN2803")
      (footprint "ULN2803")
      (fields (field (name "SOURCE") "电源模块.SCHLIB"))
      (libsource (lib "DigiPCBA Workspace") (part "ULN2803"))
    )
    (comp (ref "U9")
      (value "TLP185GB")
      (footprint "TLP185GB")
      (fields (field (name "SOURCE") "电源模块.SCHLIB"))
      (libsource (lib "DigiPCBA Workspace") (part "TLP185GB"))
    )
    (comp (ref "U10")
      (value "TLP185GB")
      (footprint "TLP185GB")
      (fields (field (name "SOURCE") "电源模块.SCHLIB"))
      (libsource (lib "DigiPCBA Workspace") (part "TLP185GB"))
    )
    (comp (ref "U11")
      (value "TLP185GB")
      (footprint "TLP185GB")
      (fields (field (name "SOURCE") "电源模块.SCHLIB"))
      (libsource (lib "DigiPCBA Workspace") (part "TLP185GB"))
    )
    (comp (ref "U12")
      (value "CAT6219-330TD")
      (footprint "SOT-23-5")
      (description "3.3V 500mA LDO")
      (libsource (lib "DigiPCBA Workspace") (part "CAT6219-330TD"))
    )
    (comp (ref "U13")
      (value "B_D-1WR2")
      (footprint "B_D-1WR2")
      (description "B2424D-1WR2")
      (fields (field (name "SOURCE") "电源模块.SCHLIB"))
      (libsource (lib "DigiPCBA Workspace") (part "B_D-1WR2"))
    )
    (comp (ref "U14")
      (value "LAN8720A")
      (footprint "QFN24")
      (description "ETH PHY")
      (libsource (lib "DigiPCBA Workspace") (part "LAN8720"))
    )
    (comp (ref "U15")
      (value "CH340G")
      (footprint "CH340")
      (fields (field (name "SOURCE") "主控芯片.SCHLIB"))
      (libsource (lib "DigiPCBA Workspace") (part "CH340G"))
    )
    (comp (ref "U16")
      (value "MP2359")
      (footprint "SOT-23-6")
      (description "DC DC Step Down IC")
      (libsource (lib "DigiPCBA Workspace") (part "MP2359"))
    )
    (comp (ref "U17")
      (value "W25Q256")
      (footprint "WSON8")
      (description "W25Q128")
      (libsource (lib "DigiPCBA Workspace") (part "W25Q128"))
    )
    (comp (ref "U18")
      (value "24C02")
      (footprint "SOP-8")
      (description "EEPROM")
      (libsource (lib "DigiPCBA Workspace") (part "24C256"))
    )
    (comp (ref "U19") (value "BC25") (footprint "BC28") (libsource (lib "TEST") (part "BC25")))
    (comp (ref "U20")
      (value "6N137")
      (footprint "6N137")
      (description "6N137 小封装,HCPL-0600 600 贴片SOP-8,高速TTL兼容光耦 白色小体积")
      (libsource (lib "Integrated_Library3") (part "6N137"))
    )
    (comp (ref "U21")
      (value "6N137")
      (footprint "6N137")
      (description "6N137 小封装,HCPL-0600 600 贴片SOP-8,高速TTL兼容光耦 白色小体积")
      (libsource (lib "Integrated_Library3") (part "6N137"))
    )
    (comp (ref "U22")
      (value "6N137")
      (footprint "6N137")
      (description "6N137 小封装,HCPL-0600 600 贴片SOP-8,高速TTL兼容光耦 白色小体积")
      (libsource (lib "Integrated_Library3") (part "6N137"))
    )
    (comp (ref "U23")
      (value "6N137")
      (footprint "6N137")
      (description "6N137 小封装,HCPL-0600 600 贴片SOP-8,高速TTL兼容光耦 白色小体积")
      (libsource (lib "Integrated_Library3") (part "6N137"))
    )
    (comp (ref "U24")
      (value "MCP3204")
      (footprint "MCP3204")
      (description "MCP3204-BI/SL 贴片SOP14")
      (libsource (lib "Integrated_Library3") (part "MCP3204"))
    )
    (comp (ref "U25") (value "B_D-1WR2") (footprint "B_D-1WR2") (libsource (lib "电源模块") (part "B_D-1WR2")))
    (comp (ref "U26")
      (value "REF198-E")
      (footprint "REF198")
      (libsource (lib "DigiPCBA Workspace") (part "REF198"))
    )
    (comp (ref "USB1")
      (value "USB")
      (footprint "USB-mirco")
      (fields (field (name "SOURCE") "主控芯片.SCHLIB"))
      (libsource (lib "DigiPCBA Workspace") (part "USB"))
    )
    (comp (ref "Y1")
      (value "XTAL-32.768Khz")
      (footprint "XTAL3215")
      (description "普通晶振")
      (fields (field (name "PUBLISHER") "Altium Limited"))
      (libsource (lib "DigiPCBA Workspace") (part "XTAL-32.768Khz"))
    )
    (comp (ref "Y2")
      (value "25MHz")
      (footprint "XTAL3225")
      (description "3225贴片无源晶振")
      (libsource (lib "DigiPCBA Workspace") (part "XTAL_3225"))
    )
    (comp (ref "Y3")
      (value "12MHz")
      (footprint "插针二脚晶振")
      (fields (field (name "SOURCE") "主控芯片.SCHLIB"))
      (libsource (lib "DigiPCBA Workspace") (part "XTAL_1"))
    )
    (comp (ref "Y4")
      (value "25MHz")
      (footprint "XTAL_US")
      (description "Crystal Oscillator")
      (fields (field (name "PUBLISHER") "Altium Limited"))
      (libsource (lib "DigiPCBA Workspace") (part "XTAL"))
    )
  )
  (nets
    (net (code "1") (name "/AI1+") (class "Default")
      (node (ref "P1") (pin "4") (pinfunction "4_4") (pintype "passive"))
      (node (ref "R55") (pin "1") (pinfunction "1_1") (pintype "passive"))
      (node (ref "R58") (pin "1") (pinfunction "1_1") (pintype "passive"))
    )
    (net (code "2") (name "/AI2+") (class "Default")
      (node (ref "P1") (pin "2") (pinfunction "2_2") (pintype "passive"))
      (node (ref "R56") (pin "1") (pinfunction "1_1") (pintype "passive"))
      (node (ref "R59") (pin "1") (pinfunction "1_1") (pintype "passive"))
    )
    (net (code "3") (name "/BEEP") (class "Default")
      (node (ref "R10") (pin "1") (pinfunction "1_1") (pintype "passive"))
      (node (ref "U2") (pin "47") (pinfunction "PB1_47") (pintype "bidirectional"))
    )
    (net (code "4") (name "/BOOT0") (class "Default")
      (node (ref "R17") (pin "1") (pinfunction "1_1") (pintype "passive"))
      (node (ref "R40") (pin "1") (pinfunction "1_1") (pintype "passive"))
      (node (ref "U2") (pin "138") (pinfunction "BOOT0_138") (pintype "input"))
    )
    (net (code "5") (name "/BOOT1") (class "Default")
      (node (ref "R1") (pin "2") (pinfunction "2_2") (pintype "passive"))
      (node (ref "U2") (pin "48") (pinfunction "PB2-BOOT1(PB2)_48") (pintype "bidirectional"))
    )
    (net (code "6") (name "/CH340D+") (class "Default")
      (node (ref "U15") (pin "5") (pinfunction "D+_5") (pintype "power_in"))
      (node (ref "USB1") (pin "3") (pinfunction "D+_3") (pintype "power_in"))
    )
    (net (code "7") (name "/CH340D-") (class "Default")
      (node (ref "U15") (pin "6") (pinfunction "D-_6") (pintype "power_in"))
      (node (ref "USB1") (pin "2") (pinfunction "D-_2") (pintype "power_in"))
    )
    (net (code "8") (name "/CLK1") (class "Default")
      (node (ref "R48") (pin "1") (pinfunction "1_1") (pintype "passive"))
      (node (ref "U20") (pin "6") (pinfunction "OUT_6") (pintype "passive"))
      (node (ref "U24") (pin "11") (pinfunction "CLK_11") (pintype "passive"))
    )
    (net (code "9") (name "/Din1") (class "Default")
      (node (ref "R50") (pin "1") (pinfunction "1_1") (pintype "passive"))
      (node (ref "U21") (pin "6") (pinfunction "OUT_6") (pintype "passive"))
      (node (ref "U24") (pin "9") (pinfunction "Din_9") (pintype "passive"))
    )
    (net (code "10") (name "/Dout1") (class "Default")
      (node (ref "U23") (pin "3") (pinfunction "IN-_3") (pintype "passive"))
      (node (ref "U24") (pin "10") (pinfunction "Dout_10") (pintype "passive"))
    )
    (net (code "11") (name "/ETH-MDC") (class "Default")
      (node (ref "U14") (pin "13") (pinfunction "MDC_13") (pintype "passive"))
      (node (ref "U2") (pin "27") (pinfunction "PC1_27") (pintype "bidirectional"))
    )
    (net (code "12") (name "/ETH-MDIO") (class "Default")
      (node (ref "R28") (pin "1") (pinfunction "1_1") (pintype "passive"))
      (node (ref "U2") (pin "36") (pinfunction "PA2_36") (pintype "bidirectional"))
    )
    (net (code "13") (name "/ETH-RESET") (class "Default")
      (node (ref "U14") (pin "15") (pinfunction "nRST_15") (pintype "passive"))
      (node (ref "U2") (pin "46") (pinfunction "PB0_46") (pintype "bidirectional"))
    )
    (net (code "14") (name "/FMC-A0") (class "Default")
      (node (ref "U1") (pin "23") (pinfunction "A0_23") (pintype "input"))
      (node (ref "U2") (pin "10") (pinfunction "PF0_10") (pintype "bidirectional"))
    )
    (net (code "15") (name "/FMC-A1") (class "Default")
      (node (ref "U1") (pin "24") (pinfunction "A1_24") (pintype "input"))
      (node (ref "U2") (pin "11") (pinfunction "PF1_11") (pintype "bidirectional"))
    )
    (net (code "16") (name "/FMC-A2") (class "Default")
      (node (ref "U1") (pin "25") (pinfunction "A2_25") (pintype "input"))
      (node (ref "U2") (pin "12") (pinfunction "PF2_12") (pintype "bidirectional"))
    )
    (net (code "17") (name "/FMC-A3") (class "Default")
      (node (ref "U1") (pin "26") (pinfunction "A3_26") (pintype "input"))
      (node (ref "U2") (pin "13") (pinfunction "PF3_13") (pintype "bidirectional"))
    )
    (net (code "18") (name "/FMC-A4") (class "Default")
      (node (ref "U1") (pin "29") (pinfunction "A4_29") (pintype "input"))
      (node (ref "U2") (pin "14") (pinfunction "PF4_14") (pintype "bidirectional"))
    )
    (net (code "19") (name "/FMC-A5") (class "Default")
      (node (ref "U1") (pin "30") (pinfunction "A5_30") (pintype "input"))
      (node (ref "U2") (pin "15") (pinfunction "PF5_15") (pintype "bidirectional"))
    )
    (net (code "20") (name "/FMC-A6") (class "Default")
      (node (ref "U1") (pin "31") (pinfunction "A6_31") (pintype "input"))
      (node (ref "U2") (pin "50") (pinfunction "PF12_50") (pintype "bidirectional"))
    )
    (net (code "21") (name "/FMC-A7") (class "Default")
      (node (ref "U1") (pin "32") (pinfunction "A7_32") (pintype "input"))
      (node (ref "U2") (pin "53") (pinfunction "PF13_53") (pintype "bidirectional"))
    )
    (net (code "22") (name "/FMC-A8") (class "Default")
      (node (ref "U1") (pin "33") (pinfunction "A8_33") (pintype "input"))
      (node (ref "U2") (pin "54") (pinfunction "PF14_54") (pintype "bidirectional"))
    )
    (net (code "23") (name "/FMC-A9") (class "Default")
      (node (ref "U1") (pin "34") (pinfunction "A9_34") (pintype "input"))
      (node (ref "U2") (pin "55") (pinfunction "PF15_55") (pintype "bidirectional"))
    )
    (net (code "24") (name "/FMC-A10") (class "Default")
      (node (ref "U1") (pin "22") (pinfunction "A10_22") (pintype "input"))
      (node (ref "U2") (pin "56") (pinfunction "PG0_56") (pintype "bidirectional"))
    )
    (net (code "25") (name "/FMC-A11") (class "Default")
      (node (ref "U1") (pin "35") (pinfunction "A11_35") (pintype "input"))
      (node (ref "U2") (pin "57") (pinfunction "PG1_57") (pintype "bidirectional"))
    )
    (net (code "26") (name "/FMC-A12") (class "Default")
      (node (ref "U1") (pin "36") (pinfunction "A12/NC_36") (pintype "input"))
      (node (ref "U2") (pin "87") (pinfunction "PG2_87") (pintype "bidirectional"))
    )
    (net (code "27") (name "/FMC-A18") (class "Default")
      (node (ref "TFTLCD1") (pin "2") (pinfunction "RS_2") (pintype "passive"))
      (node (ref "U2") (pin "82") (pinfunction "PD13_82") (pintype "bidirectional"))
    )
    (net (code "28") (name "/FMC-BA0") (class "Default")
      (node (ref "U1") (pin "20") (pinfunction "BA0_20") (pintype "input"))
      (node (ref "U2") (pin "89") (pinfunction "PG4_89") (pintype "bidirectional"))
    )
    (net (code "29") (name "/FMC-BA1") (class "Default")
      (node (ref "U1") (pin "21") (pinfunction "BA1_21") (pintype "bidirectional"))
      (node (ref "U2") (pin "90") (pinfunction "PG5_90") (pintype "bidirectional"))
    )
    (net (code "30") (name "/FMC-D0") (class "Default")
      (node (ref "TFTLCD1") (pin "6") (pinfunction "DB0_6") (pintype "passive"))
      (node (ref "U1") (pin "2") (pinfunction "DQ0_2") (pintype "bidirectional"))
      (node (ref "U2") (pin "85") (pinfunction "PD14_85") (pintype "bidirectional"))
    )
    (net (code "31") (name "/FMC-D1") (class "Default")
      (node (ref "TFTLCD1") (pin "7") (pinfunction "DB1_7") (pintype "passive"))
      (node (ref "U1") (pin "4") (pinfunction "DQ1_4") (pintype "bidirectional"))
      (node (ref "U2") (pin "86") (pinfunction "PD15_86") (pintype "bidirectional"))
    )
    (net (code "32") (name "/FMC-D2") (class "Default")
      (node (ref "TFTLCD1") (pin "8") (pinfunction "DB2_8") (pintype "passive"))
      (node (ref "U1") (pin "5") (pinfunction "DQ2_5") (pintype "bidirectional"))
      (node (ref "U2") (pin "114") (pinfunction "PD0_114") (pintype "bidirectional"))
    )
    (net (code "33") (name "/FMC-D3") (class "Default")
      (node (ref "TFTLCD1") (pin "9") (pinfunction "DB3_9") (pintype "passive"))
      (node (ref "U1") (pin "7") (pinfunction "DQ3_7") (pintype "bidirectional"))
      (node (ref "U2") (pin "115") (pinfunction "PD1_115") (pintype "bidirectional"))
    )
    (net (code "34") (name "/FMC-D4") (class "Default")
      (node (ref "TFTLCD1") (pin "10") (pinfunction "DB4_10") (pintype "passive"))
      (node (ref "U1") (pin "8") (pinfunction "DQ4_8") (pintype "bidirectional"))
      (node (ref "U2") (pin "58") (pinfunction "PE7_58") (pintype "bidirectional"))
    )
    (net (code "35") (name "/FMC-D5") (class "Default")
      (node (ref "TFTLCD1") (pin "11") (pinfunction "DB5_11") (pintype "passive"))
      (node (ref "U1") (pin "10") (pinfunction "DQ5_10") (pintype "bidirectional"))
      (node (ref "U2") (pin "59") (pinfunction "PE8_59") (pintype "bidirectional"))
    )
    (net (code "36") (name "/FMC-D6") (class "Default")
      (node (ref "TFTLCD1") (pin "12") (pinfunction "DB6_12") (pintype "passive"))
      (node (ref "U1") (pin "11") (pinfunction "DQ6_11") (pintype "bidirectional"))
      (node (ref "U2") (pin "60") (pinfunction "PE9_60") (pintype "bidirectional"))
    )
    (net (code "37") (name "/FMC-D7") (class "Default")
      (node (ref "TFTLCD1") (pin "13") (pinfunction "DB7_13") (pintype "passive"))
      (node (ref "U1") (pin "13") (pinfunction "DQ7_13") (pintype "bidirectional"))
      (node (ref "U2") (pin "63") (pinfunction "PE10_63") (pintype "bidirectional"))
    )
    (net (code "38") (name "/FMC-D8") (class "Default")
      (node (ref "TFTLCD1") (pin "14") (pinfunction "DB8_14") (pintype "passive"))
      (node (ref "U1") (pin "42") (pinfunction "DQ8_42") (pintype "bidirectional"))
      (node (ref "U2") (pin "64") (pinfunction "PE11_64") (pintype "bidirectional"))
    )
    (net (code "39") (name "/FMC-D9") (class "Default")
      (node (ref "TFTLCD1") (pin "15") (pinfunction "DB9_15") (pintype "passive"))
      (node (ref "U1") (pin "44") (pinfunction "DQ9_44") (pintype "bidirectional"))
      (node (ref "U2") (pin "65") (pinfunction "PE12_65") (pintype "bidirectional"))
    )
    (net (code "40") (name "/FMC-D10") (class "Default")
      (node (ref "TFTLCD1") (pin "16") (pinfunction "DB10_16") (pintype "passive"))
      (node (ref "U1") (pin "45") (pinfunction "DQ10_45") (pintype "bidirectional"))
      (node (ref "U2") (pin "66") (pinfunction "PE13_66") (pintype "bidirectional"))
    )
    (net (code "41") (name "/FMC-D11") (class "Default")
      (node (ref "TFTLCD1") (pin "17") (pinfunction "DB11_17") (pintype "passive"))
      (node (ref "U1") (pin "47") (pinfunction "DQ11_47") (pintype "bidirectional"))
      (node (ref "U2") (pin "67") (pinfunction "PE14_67") (pintype "bidirectional"))
    )
    (net (code "42") (name "/FMC-D12") (class "Default")
      (node (ref "TFTLCD1") (pin "18") (pinfunction "DB12_18") (pintype "passive"))
      (node (ref "U1") (pin "48") (pinfunction "DQ12_48") (pintype "bidirectional"))
      (node (ref "U2") (pin "68") (pinfunction "PE15_68") (pintype "bidirectional"))
    )
    (net (code "43") (name "/FMC-D13") (class "Default")
      (node (ref "TFTLCD1") (pin "19") (pinfunction "DB13_19") (pintype "passive"))
      (node (ref "U1") (pin "50") (pinfunction "DQ13_50") (pintype "bidirectional"))
      (node (ref "U2") (pin "77") (pinfunction "PD8_77") (pintype "bidirectional"))
    )
    (net (code "44") (name "/FMC-D14") (class "Default")
      (node (ref "TFTLCD1") (pin "20") (pinfunction "DB14_20") (pintype "passive"))
      (node (ref "U1") (pin "51") (pinfunction "DQ14_51") (pintype "bidirectional"))
      (node (ref "U2") (pin "78") (pinfunction "PD9_78") (pintype "bidirectional"))
    )
    (net (code "45") (name "/FMC-D15") (class "Default")
      (node (ref "TFTLCD1") (pin "21") (pinfunction "DB15_21") (pintype "passive"))
      (node (ref "U1") (pin "53") (pinfunction "DQ15_53") (pintype "bidirectional"))
      (node (ref "U2") (pin "79") (pinfunction "PD10_79") (pintype "bidirectional"))
    )
    (net (code "46") (name "/FMC-NBL0") (class "Default")
      (node (ref "U1") (pin "15") (pinfunction "LDQM_15") (pintype "input"))
      (node (ref "U2") (pin "141") (pinfunction "PE0_141") (pintype "bidirectional"))
    )
    (net (code "47") (name "/FMC-NBL1") (class "Default")
      (node (ref "U1") (pin "39") (pinfunction "UDQM_39") (pintype "input"))
      (node (ref "U2") (pin "142") (pinfunction "PE1_142") (pintype "bidirectional"))
    )
    (net (code "48") (name "/FMC-NE1") (class "Default")
      (node (ref "TFTLCD1") (pin "1") (pinfunction "CS_1") (pintype "passive"))
      (node (ref "U2") (pin "123") (pinfunction "PD7_123") (pintype "bidirectional"))
    )
    (net (code "49") (name "/FMC-NOE") (class "Default")
      (node (ref "TFTLCD1") (pin "4") (pinfunction "RD_4") (pintype "passive"))
      (node (ref "U2") (pin "118") (pinfunction "PD4_118") (pintype "bidirectional"))
    )
    (net (code "50") (name "/FMC-NWE") (class "Default")
      (node (ref "TFTLCD1") (pin "3") (pinfunction "WR_3") (pintype "passive"))
      (node (ref "U2") (pin "119") (pinfunction "PD5_119") (pintype "bidirectional"))
    )
    (net (code "51") (name "/FMC-SDCKE0") (class "Default")
      (node (ref "U1") (pin "37") (pinfunction "CKE_37") (pintype "input"))
      (node (ref "U2") (pin "29") (pinfunction "PC3_29") (pintype "bidirectional"))
    )
    (net (code "52") (name "/FMC-SDCLK") (class "Default")
      (node (ref "U1") (pin "38") (pinfunction "CLK_38") (pintype "input"))
      (node (ref "U2") (pin "93") (pinfunction "PG8_93") (pintype "bidirectional"))
    )
    (net (code "53") (name "/FMC-SDNCAS") (class "Default")
      (node (ref "U1") (pin "17") (pinfunction "~{CAS}_17") (pintype "input"))
      (node (ref "U2") (pin "132") (pinfunction "PG15_132") (pintype "bidirectional"))
    )
    (net (code "54") (name "/FMC-SDNE0") (class "Default")
      (node (ref "R8") (pin "2") (pinfunction "2_2") (pintype "passive"))
      (node (ref "U1") (pin "19") (pinfunction "~{CS}_19") (pintype "input"))
      (node (ref "U2") (pin "28") (pinfunction "PC2_28") (pintype "bidirectional"))
    )
    (net (code "55") (name "/FMC-SDNRAS") (class "Default")
      (node (ref "U1") (pin "18") (pinfunction "~{RAS}_18") (pintype "passive"))
      (node (ref "U2") (pin "49") (pinfunction "PF11_49") (pintype "bidirectional"))
    )
    (net (code "56") (name "/FMC-SDNWE") (class "Default")
      (node (ref "U1") (pin "16") (pinfunction "~{WE}_16") (pintype "input"))
      (node (ref "U2") (pin "26") (pinfunction "PC0_26") (pintype "bidirectional"))
    )
    (net (code "57") (name "/GND-5") (class "Default")
      (node (ref "C76") (pin "2") (pinfunction "2_2") (pintype "passive"))
      (node (ref "U25") (pin "1") (pinfunction "GND_1") (pintype "passive"))
    )
    (net (code "58") (name "/GND-24") (class "Default")
      (node (ref "C40") (pin "2") (pinfunction "2_2") (pintype "passive"))
      (node (ref "P1") (pin "6") (pinfunction "6_6") (pintype "passive"))
      (node (ref "U13") (pin "1") (pinfunction "GND_1") (pintype "passive"))
    )
    (net (code "59") (name "/I2C1-SCL") (class "Default")
      (node (ref "R44") (pin "1") (pinfunction "1_1") (pintype "passive"))
      (node (ref "U18") (pin "6") (pinfunction "SCL_6") (pintype "passive"))
      (node (ref "U2") (pin "139") (pinfunction "PB8_139") (pintype "bidirectional"))
    )
    (net (code "60") (name "/I2C1-SDA") (class "Default")
      (node (ref "R47") (pin "1") (pinfunction "1_1") (pintype "passive"))
      (node (ref "U18") (pin "5") (pinfunction "SDA_5") (pintype "passive"))
      (node (ref "U2") (pin "140") (pinfunction "PB9_140") (pintype "bidirectional"))
    )
    (net (code "61") (name "/LCD-BL") (class "Default")
      (node (ref "R37") (pin "2") (pinfunction "2_2") (pintype "passive"))
      (node (ref "TFTLCD1") (pin "23") (pinfunction "BL_23") (pintype "passive"))
      (node (ref "U2") (pin "76") (pinfunction "PB15_76") (pintype "bidirectional"))
    )
    (net (code "62") (name "/LED4{slash}MCU-Relay6") (class "Default")
      (node (ref "R24") (pin "1") (pinfunction "1_1") (pintype "passive"))
      (node (ref "U2") (pin "103") (pinfunction "PA11_103") (pintype "bidirectional"))
    )
    (net (code "63") (name "/LINK-LED") (class "Default")
      (node (ref "EARTHNET1") (pin "12") (pinfunction "LED(Y)_A_12") (pintype "passive"))
      (node (ref "R34") (pin "1") (pinfunction "1_1") (pintype "passive"))
      (node (ref "U14") (pin "3") (pinfunction "LED1/REGOFF_3") (pintype "passive"))
    )
    (net (code "64") (name "/L_MISO") (class "Default")
      (node (ref "U2") (pin "134") (pinfunction "PB4(NJTRST)_134") (pintype "bidirectional"))
      (node (ref "U3") (pin "22") (pinfunction "MISO_22") (pintype "passive"))
    )
    (net (code "65") (name "/L_MOSI") (class "Default")
      (node (ref "U2") (pin "122") (pinfunction "PD6_122") (pintype "bidirectional"))
      (node (ref "U3") (pin "23") (pinfunction "MOSI_23") (pintype "passive"))
    )
    (net (code "66") (name "/L_NSS") (class "Default")
      (node (ref "U2") (pin "110") (pinfunction "PA15(JTDI)_110") (pintype "bidirectional"))
      (node (ref "U3") (pin "25") (pinfunction "NSS_25") (pintype "passive"))
    )
    (net (code "67") (name "/L_RST") (class "Default")
      (node (ref "U2") (pin "100") (pinfunction "PA8_100") (pintype "bidirectional"))
      (node (ref "U3") (pin "21") (pinfunction "NRST_21") (pintype "passive"))
    )
    (net (code "68") (name "/L_RX_EN") (class "Default")
      (node (ref "U2") (pin "102") (pinfunction "PA10_102") (pintype "bidirectional"))
      (node (ref "U3") (pin "6") (pinfunction "RXEN_6") (pintype "passive"))
    )
    (net (code "69") (name "/L_SCK") (class "Default")
      (node (ref "U2") (pin "133") (pinfunction "PB3(JTDO/TRACESWO)_133") (pintype "bidirectional"))
      (node (ref "U3") (pin "24") (pinfunction "SCLK_24") (pintype "passive"))
    )
    (net (code "70") (name "/L_TX_EN") (class "Default")
      (node (ref "U2") (pin "101") (pinfunction "PA9_101") (pintype "bidirectional"))
      (node (ref "U3") (pin "7") (pinfunction "TXEN_7") (pintype "passive"))
    )
    (net (code "71") (name "/MCU-Relay1") (class "Default")
      (node (ref "R11") (pin "1") (pinfunction "1_1") (pintype "passive"))
      (node (ref "U2") (pin "128") (pinfunction "PG13_128") (pintype "bidirectional"))
    )
    (net (code "72") (name "/MCU-Relay2") (class "Default")
      (node (ref "R13") (pin "1") (pinfunction "1_1") (pintype "passive"))
      (node (ref "U2") (pin "127") (pinfunction "PG12_127") (pintype "bidirectional"))
    )
    (net (code "73") (name "/MCU-Relay3") (class "Default")
      (node (ref "R15") (pin "1") (pinfunction "1_1") (pintype "passive"))
      (node (ref "U2") (pin "126") (pinfunction "PG11_126") (pintype "bidirectional"))
    )
    (net (code "74") (name "/MCU-Relay4") (class "Default")
      (node (ref "R18") (pin "1") (pinfunction "1_1") (pintype "passive"))
      (node (ref "U2") (pin "125") (pinfunction "PG10_125") (pintype "bidirectional"))
    )
    (net (code "75") (name "/MCU-Relay5") (class "Default")
      (node (ref "R22") (pin "1") (pinfunction "1_1") (pintype "passive"))
      (node (ref "U2") (pin "104") (pinfunction "PA12_104") (pintype "bidirectional"))
    )
    (net (code "76") (name "/RESET") (class "Default")
      (node (ref "C35") (pin "1") (pinfunction "1_1") (pintype "passive"))
      (node (ref "D3") (pin "1") (pinfunction "A_1") (pintype "passive"))
      (node (ref "R21") (pin "1") (pinfunction "1_1") (pintype "passive"))
      (node (ref "RESET1") (pin "1") (pinfunction "1_1") (pintype "passive"))
      (node (ref "TFTLCD1") (pin "5") (pinfunction "RST_5") (pintype "passive"))
      (node (ref "U19") (pin "5") (pinfunction "RST_5") (pintype "passive"))
      (node (ref "U2") (pin "25") (pinfunction "NRST_25") (pintype "bidirectional"))
    )
    (net (code "77") (name "/RMII-CRS-DV") (class "Default")
      (node (ref "U14") (pin "11") (pinfunction "CSR_DV/MODE2_11") (pintype "passive"))
      (node (ref "U2") (pin "43") (pinfunction "PA7_43") (pintype "bidirectional"))
    )
    (net (code "78") (name "/RMII-REF-CLK") (class "Default")
      (node (ref "U14") (pin "14") (pinfunction "nINT/REFCLKO_14") (pintype "passive"))
      (node (ref "U2") (pin "35") (pinfunction "PA1_35") (pintype "bidirectional"))
    )
    (net (code "79") (name "/RMII-RXD0") (class "Default")
      (node (ref "U14") (pin "8") (pinfunction "RXD0/MODE0_8") (pintype "passive"))
      (node (ref "U2") (pin "44") (pinfunction "PC4_44") (pintype "bidirectional"))
    )
    (net (code "80") (name "/RMII-RXD1") (class "Default")
      (node (ref "U14") (pin "7") (pinfunction "RXD1/MODE1_7") (pintype "passive"))
      (node (ref "U2") (pin "45") (pinfunction "PC5_45") (pintype "bidirectional"))
    )
    (net (code "81") (name "/RMII-TX-EN") (class "Default")
      (node (ref "U14") (pin "16") (pinfunction "TXEN_16") (pintype "passive"))
      (node (ref "U2") (pin "70") (pinfunction "PB11_70") (pintype "bidirectional"))
    )
    (net (code "82") (name "/RMII-TXD0") (class "Default")
      (node (ref "U14") (pin "17") (pinfunction "TXD0_17") (pintype "passive"))
      (node (ref "U2") (pin "73") (pinfunction "PB12_73") (pintype "bidirectional"))
    )
    (net (code "83") (name "/RMII-TXD1") (class "Default")
      (node (ref "U14") (pin "18") (pinfunction "TXD1_18") (pintype "passive"))
      (node (ref "U2") (pin "74") (pinfunction "PB13_74") (pintype "bidirectional"))
    )
    (net (code "84") (name "/Relay1+") (class "Default")
      (node (ref "HF1") (pin "3") (pintype "passive"))
      (node (ref "P2") (pin "1") (pinfunction "1_1") (pintype "passive"))
    )
    (net (code "85") (name "/Relay1-") (class "Default")
      (node (ref "HF1") (pin "4") (pintype "passive"))
      (node (ref "P2") (pin "2") (pinfunction "2_2") (pintype "passive"))
    )
    (net (code "86") (name "/Relay2+") (class "Default")
      (node (ref "HF2") (pin "3") (pintype "passive"))
      (node (ref "P2") (pin "3") (pinfunction "3_3") (pintype "passive"))
    )
    (net (code "87") (name "/Relay2-") (class "Default")
      (node (ref "HF2") (pin "4") (pintype "passive"))
      (node (ref "P2") (pin "4") (pinfunction "4_4") (pintype "passive"))
    )
    (net (code "88") (name "/Relay3+") (class "Default")
      (node (ref "HF3") (pin "3") (pintype "passive"))
      (node (ref "P2") (pin "5") (pinfunction "5_5") (pintype "passive"))
    )
    (net (code "89") (name "/Relay3-") (class "Default")
      (node (ref "HF3") (pin "4") (pintype "passive"))
      (node (ref "P2") (pin "6") (pinfunction "6_6") (pintype "passive"))
    )
    (net (code "90") (name "/Relay4+") (class "Default")
      (node (ref "HF4") (pin "3") (pintype "passive"))
      (node (ref "P2") (pin "7") (pinfunction "7_7") (pintype "passive"))
    )
    (net (code "91") (name "/Relay4-") (class "Default")
      (node (ref "HF4") (pin "4") (pintype "passive"))
      (node (ref "P2") (pin "8") (pinfunction "8_8") (pintype "passive"))
    )
    (net (code "92") (name "/Relay5+") (class "Default")
      (node (ref "HF5") (pin "3") (pintype "passive"))
      (node (ref "P2") (pin "9") (pinfunction "9_9") (pintype "passive"))
    )
    (net (code "93") (name "/Relay5-") (class "Default")
      (node (ref "HF5") (pin "4") (pintype "passive"))
      (node (ref "P2") (pin "10") (pinfunction "10_10") (pintype "passive"))
    )
    (net (code "94") (name "/Relay6+") (class "Default")
      (node (ref "HF6") (pin "3") (pintype "passive"))
      (node (ref "P2") (pin "11") (pinfunction "11_11") (pintype "passive"))
    )
    (net (code "95") (name "/Relay6-") (class "Default")
      (node (ref "HF6") (pin "4") (pintype "passive"))
      (node (ref "P2") (pin "12") (pinfunction "12_12") (pintype "passive"))
    )
    (net (code "96") (name "/SDIO-CLK") (class "Default")
      (node (ref "TF1") (pin "5") (pinfunction "CLK_5") (pintype "passive"))
      (node (ref "U2") (pin "113") (pinfunction "PC12_113") (pintype "bidirectional"))
    )
    (net (code "97") (name "/SDIO-CMD") (class "Default")
      (node (ref "R2") (pin "1") (pinfunction "1_1") (pintype "passive"))
      (node (ref "TF1") (pin "3") (pinfunction "CMD_3") (pintype "passive"))
      (node (ref "U2") (pin "116") (pinfunction "PD2_116") (pintype "bidirectional"))
    )
    (net (code "98") (name "/SDIO-D0") (class "Default")
      (node (ref "R6") (pin "1") (pinfunction "1_1") (pintype "passive"))
      (node (ref "TF1") (pin "7") (pinfunction "DATA0_7") (pintype "passive"))
      (node (ref "U2") (pin "98") (pinfunction "PC8_98") (pintype "bidirectional"))
    )
    (net (code "99") (name "/SDIO-D1") (class "Default")
      (node (ref "R5") (pin "1") (pinfunction "1_1") (pintype "passive"))
      (node (ref "TF1") (pin "8") (pinfunction "DATA1_8") (pintype "passive"))
      (node (ref "U2") (pin "99") (pinfunction "PC9_99") (pintype "bidirectional"))
    )
    (net (code "100") (name "/SDIO-D2") (class "Default")
      (node (ref "R4") (pin "1") (pinfunction "1_1") (pintype "passive"))
      (node (ref "TF1") (pin "1") (pinfunction "DATA2_1") (pintype "passive"))
      (node (ref "U2") (pin "111") (pinfunction "PC10_111") (pintype "bidirectional"))
    )
    (net (code "101") (name "/SDIO-D3") (class "Default")
      (node (ref "R3") (pin "1") (pinfunction "1_1") (pintype "passive"))
      (node (ref "TF1") (pin "2") (pinfunction "CM/DATA3_2") (pintype "passive"))
      (node (ref "U2") (pin "112") (pinfunction "PC11_112") (pintype "bidirectional"))
    )
    (net (code "102") (name "/SPEED-LED") (class "Default")
      (node (ref "EARTHNET1") (pin "9") (pinfunction "LED(G)_A_9") (pintype "passive"))
      (node (ref "R38") (pin "1") (pinfunction "1_1") (pintype "passive"))
      (node (ref "U14") (pin "2") (pinfunction "LED2/nINTSEL_2") (pintype "passive"))
    )
    (net (code "103") (name "/SPI1-CLK") (class "Default")
      (node (ref "U17") (pin "6") (pinfunction "CLK_6") (pintype "passive"))
      (node (ref "U2") (pin "41") (pinfunction "PA5_41") (pintype "bidirectional"))
    )
    (net (code "104") (name "/SPI1-MISO") (class "Default")
      (node (ref "U17") (pin "2") (pinfunction "SO(IO1)_2") (pintype "passive"))
      (node (ref "U2") (pin "42") (pinfunction "PA6_42") (pintype "bidirectional"))
    )
    (net (code "105") (name "/SPI1-MOSI") (class "Default")
      (node (ref "U17") (pin "5") (pinfunction "SI(IO0)_5") (pintype "power_in"))
      (node (ref "U2") (pin "135") (pinfunction "PB5_135") (pintype "bidirectional"))
    )
    (net (code "106") (name "/SPI1-NSS") (class "Default")
      (node (ref "U17") (pin "1") (pinfunction "~{CS}_1") (pintype "passive"))
      (node (ref "U2") (pin "40") (pinfunction "PA4_40") (pintype "bidirectional"))
    )
    (net (code "107") (name "/SPI5-MISO") (class "Default")
      (node (ref "R54") (pin "1") (pinfunction "1_1") (pintype "passive"))
      (node (ref "U2") (pin "20") (pinfunction "PF8_20") (pintype "bidirectional"))
      (node (ref "U23") (pin "6") (pinfunction "OUT_6") (pintype "passive"))
    )
    (net (code "108") (name "/SPI5-MOSI") (class "Default")
      (node (ref "U2") (pin "21") (pinfunction "PF9_21") (pintype "bidirectional"))
      (node (ref "U21") (pin "3") (pinfunction "IN-_3") (pintype "passive"))
    )
    (net (code "109") (name "/SPI5-NSS") (class "Default")
      (node (ref "U2") (pin "18") (pinfunction "PF6_18") (pintype "bidirectional"))
      (node (ref "U22") (pin "3") (pinfunction "IN-_3") (pintype "passive"))
    )
    (net (code "110") (name "/SPI5-SCK") (class "Default")
      (node (ref "U2") (pin "19") (pinfunction "PF7_19") (pintype "bidirectional"))
      (node (ref "U20") (pin "3") (pinfunction "IN-_3") (pintype "passive"))
    )
    (net (code "111") (name "/T-CS") (class "Default")
      (node (ref "TFTLCD1") (pin "33") (pinfunction "T_CS_33") (pintype "passive"))
      (node (ref "U2") (pin "88") (pinfunction "PG3_88") (pintype "bidirectional"))
    )
    (net (code "112") (name "/T-MOSI") (class "Default")
      (node (ref "TFTLCD1") (pin "30") (pinfunction "MOSI_30") (pintype "passive"))
      (node (ref "U2") (pin "80") (pinfunction "PD11_80") (pintype "bidirectional"))
    )
    (net (code "113") (name "/T-PEN") (class "Default")
      (node (ref "TFTLCD1") (pin "31") (pinfunction "T_PEN_31") (pintype "passive"))
      (node (ref "U2") (pin "91") (pinfunction "PG6_91") (pintype "bidirectional"))
    )
    (net (code "114") (name "/T-SCK") (class "Default")
      (node (ref "TFTLCD1") (pin "34") (pinfunction "CLK_34") (pintype "passive"))
      (node (ref "U2") (pin "81") (pinfunction "PD12_81") (pintype "bidirectional"))
    )
    (net (code "115") (name "/TPRX+") (class "Default")
      (node (ref "C68") (pin "2") (pinfunction "2_2") (pintype "passive"))
      (node (ref "EARTHNET1") (pin "3") (pinfunction "RD+_3") (pintype "passive"))
      (node (ref "R31") (pin "1") (pinfunction "1_1") (pintype "passive"))
      (node (ref "U14") (pin "23") (pinfunction "RXP_23") (pintype "passive"))
    )
    (net (code "116") (name "/TPRX-") (class "Default")
      (node (ref "C69") (pin "2") (pinfunction "2_2") (pintype "passive"))
      (node (ref "EARTHNET1") (pin "6") (pinfunction "RD-_6") (pintype "passive"))
      (node (ref "R33") (pin "1") (pinfunction "1_1") (pintype "passive"))
      (node (ref "U14") (pin "22") (pinfunction "RXN_22") (pintype "passive"))
    )
    (net (code "117") (name "/TPTX+") (class "Default")
      (node (ref "C66") (pin "2") (pinfunction "2_2") (pintype "passive"))
      (node (ref "EARTHNET1") (pin "1") (pinfunction "TD+_1") (pintype "passive"))
      (node (ref "R29") (pin "1") (pinfunction "1_1") (pintype "passive"))
      (node (ref "U14") (pin "21") (pinfunction "TXP_21") (pintype "passive"))
    )
    (net (code "118") (name "/TPTX-") (class "Default")
      (node (ref "C67") (pin "2") (pinfunction "2_2") (pintype "passive"))
      (node (ref "EARTHNET1") (pin "2") (pinfunction "TD-_2") (pintype "passive"))
      (node (ref "R30") (pin "1") (pinfunction "1_1") (pintype "passive"))
      (node (ref "U14") (pin "20") (pinfunction "TXN_20") (pintype "passive"))
    )
    (net (code "119") (name "/USART1-RX") (class "Default")
      (node (ref "U15") (pin "3") (pinfunction "RXD_3") (pintype "power_in"))
      (node (ref "U2") (pin "136") (pinfunction "PB6_136") (pintype "bidirectional"))
    )
    (net (code "120") (name "/USART1-TX") (class "Default")
      (node (ref "U15") (pin "2") (pinfunction "TXD_2") (pintype "power_in"))
      (node (ref "U2") (pin "137") (pinfunction "PB7_137") (pintype "bidirectional"))
    )
    (net (code "121") (name "/USART6-RX") (class "Default")
      (node (ref "U19") (pin "5") (pinfunction "RXD_5") (pintype "passive"))
      (node (ref "U2") (pin "124") (pinfunction "PG9_124") (pintype "bidirectional"))
    )
    (net (code "122") (name "/USART6-TX") (class "Default")
      (node (ref "U19") (pin "4") (pinfunction "TXD_4") (pintype "passive"))
      (node (ref "U2") (pin "129") (pinfunction "PG14_129") (pintype "bidirectional"))
    )
    (net (code "123") (name "/VCC-24") (class "Default")
      (node (ref "C40") (pin "1") (pinfunction "1_1") (pintype "passive"))
      (node (ref "P1") (pin "5") (pinfunction "5_5") (pintype "passive"))
      (node (ref "U13") (pin "4") (pinfunction "Vin_4") (pintype "passive"))
    )
    (net (code "124") (name "/~{CS1}") (class "Default")
      (node (ref "R52") (pin "1") (pinfunction "1_1") (pintype "passive"))
      (node (ref "U22") (pin "6") (pinfunction "OUT_6") (pintype "passive"))
      (node (ref "U24") (pin "8") (pinfunction "~{CS}_8") (pintype "passive"))
    )
    (net (code "125") (name "5V-AD") (class "Default")
      (node (ref "C70") (pin "1") (pinfunction "1_1") (pintype "passive"))
      (node (ref "C71") (pin "1") (pinfunction "1_1") (pintype "passive"))
      (node (ref "C72") (pin "1") (pinfunction "1_1") (pintype "passive"))
      (node (ref "C77") (pin "1") (pinfunction "1_1") (pintype "passive"))
      (node (ref "C78") (pin "2") (pinfunction "2_2") (pintype "passive"))
      (node (ref "C79") (pin "2") (pinfunction "2_2") (pintype "passive"))
      (node (ref "R48") (pin "2") (pinfunction "2_2") (pintype "passive"))
      (node (ref "R50") (pin "2") (pinfunction "2_2") (pintype "passive"))
      (node (ref "R52") (pin "2") (pinfunction "2_2") (pintype "passive"))
      (node (ref "R53") (pin "1") (pinfunction "1_1") (pintype "passive"))
      (node (ref "R57") (pin "1") (pinfunction "1_1") (pintype "passive"))
      (node (ref "U20") (pin "7") (pinfunction "EN_7") (pintype "passive"))
      (node (ref "U20") (pin "8") (pinfunction "VCC_8") (pintype "passive"))
      (node (ref "U21") (pin "7") (pinfunction "EN_7") (pintype "passive"))
      (node (ref "U21") (pin "8") (pinfunction "VCC_8") (pintype "passive"))
      (node (ref "U22") (pin "7") (pinfunction "EN_7") (pintype "passive"))
      (node (ref "U22") (pin "8") (pinfunction "VCC_8") (pintype "passive"))
      (node (ref "U24") (pin "14") (pinfunction "Vdd_14") (pintype "passive"))
      (node (ref "U25") (pin "5") (pinfunction "+Vo_5") (pintype "passive"))
      (node (ref "U26") (pin "2") (pinfunction "VS_2") (pintype "passive"))
      (node (ref "U26") (pin "3") (pinfunction "~{SLEEP}_3") (pintype "passive"))
    )
    (net (code "126") (name "24V-Relay") (class "Default")
      (node (ref "C41") (pin "1") (pinfunction "1_1") (pintype "passive"))
      (node (ref "HF1") (pin "2") (pintype "passive"))
      (node (ref "HF2") (pin "2") (pintype "passive"))
      (node (ref "HF3") (pin "2") (pintype "passive"))
      (node (ref "HF4") (pin "2") (pintype "passive"))
      (node (ref "HF5") (pin "2") (pintype "passive"))
      (node (ref "HF6") (pin "2") (pintype "passive"))
      (node (ref "R12") (pin "2") (pinfunction "2_2") (pintype "passive"))
      (node (ref "R14") (pin "2") (pinfunction "2_2") (pintype "passive"))
      (node (ref "R16") (pin "2") (pinfunction "2_2") (pintype "passive"))
      (node (ref "R19") (pin "2") (pinfunction "2_2") (pintype "passive"))
      (node (ref "R23") (pin "2") (pinfunction "2_2") (pintype "passive"))
      (node (ref "R25") (pin "2") (pinfunction "2_2") (pintype "passive"))
      (node (ref "U13") (pin "5") (pinfunction "+Vo_5") (pintype "passive"))
      (node (ref "U8") (pin "10") (pinfunction "VCC_10") (pintype "passive"))
    )
    (net (code "127") (name "GND") (class "Default")
      (node (ref "BAT1") (pin "2") (pinfunction "GND_2") (pintype "passive"))
      (node (ref "BEEP1") (pin "2") (pinfunction "G_2") (pintype "passive"))
      (node (ref "C1") (pin "1") (pinfunction "1_1") (pintype "passive"))
      (node (ref "C10") (pin "1") (pinfunction "1_1") (pintype "passive"))
      (node (ref "C11") (pin "1") (pinfunction "1_1") (pintype "passive"))
      (node (ref "C12") (pin "1") (pinfunction "1_1") (pintype "passive"))
      (node (ref "C13") (pin "1") (pinfunction "1_1") (pintype "passive"))
      (node (ref "C14") (pin "1") (pinfunction "1_1") (pintype "passive"))
      (node (ref "C15") (pin "1") (pinfunction "1_1") (pintype "passive"))
      (node (ref "C16") (pin "1") (pinfunction "1_1") (pintype "passive"))
      (node (ref "C17") (pin "1") (pinfunction "1_1") (pintype "passive"))
      (node (ref "C18") (pin "1") (pinfunction "1_1") (pintype "passive"))
      (node (ref "C19") (pin "1") (pinfunction "1_1") (pintype "passive"))
      (node (ref "C2") (pin "1") (pintype "passive"))
      (node (ref "C20") (pin "1") (pinfunction "1_1") (pintype "passive"))
      (node (ref "C21") (pin "1") (pinfunction "1_1") (pintype "passive"))
      (node (ref "C22") (pin "1") (pinfunction "1_1") (pintype "passive"))
      (node (ref "C23") (pin "1") (pinfunction "1_1") (pintype "passive"))
      (node (ref "C24") (pin "1") (pinfunction "1_1") (pintype "passive"))
      (node (ref "C25") (pin "1") (pinfunction "1_1") (pintype "passive"))
      (node (ref "C26") (pin "1") (pinfunction "1_1") (pintype "passive"))
      (node (ref "C27") (pin "1") (pinfunction "1_1") (pintype "passive"))
      (node (ref "C28") (pin "1") (pinfunction "1_1") (pintype "passive"))
      (node (ref "C29") (pin "1") (pinfunction "1_1") (pintype "passive"))
      (node (ref "C3") (pin "1") (pinfunction "1_1") (pintype "passive"))
      (node (ref "C30") (pin "2") (pinfunction "GND_2") (pintype "passive"))
      (node (ref "C31") (pin "1") (pinfunction "1_1") (pintype "passive"))
      (node (ref "C32") (pin "1") (pinfunction "1_1") (pintype "passive"))
      (node (ref "C33") (pin "1") (pinfunction "1_1") (pintype "passive"))
      (node (ref "C34") (pin "1") (pinfunction "1_1") (pintype "passive"))
      (node (ref "C35") (pin "2") (pinfunction "2_2") (pintype "passive"))
      (node (ref "C36") (pin "1") (pinfunction "1_1") (pintype "passive"))
      (node (ref "C37") (pin "1") (pinfunction "1_1") (pintype "passive"))
      (node (ref "C38") (pin "1") (pinfunction "1_1") (pintype "passive"))
      (node (ref "C39") (pin "1") (pinfunction "1_1") (pintype "passive"))
      (node (ref "C4") (pin "1") (pinfunction "1_1") (pintype "passive"))
      (node (ref "C43") (pin "1") (pintype "passive"))
      (node (ref "C44") (pin "1") (pintype "passive"))
      (node (ref "C45") (pin "1") (pintype "passive"))
      (node (ref "C46") (pin "2") (pinfunction "GND_2") (pintype "passive"))
      (node (ref "C47") (pin "2") (pintype "passive"))
      (node (ref "C48") (pin "2") (pinfunction "2_2") (pintype "passive"))
      (node (ref "C49") (pin "1") (pintype "passive"))
      (node (ref "C5") (pin "1") (pinfunction "1_1") (pintype "passive"))
      (node (ref "C50") (pin "2") (pinfunction "2_2") (pintype "passive"))
      (node (ref "C51") (pin "1") (pintype "passive"))
      (node (ref "C52") (pin "1") (pintype "passive"))
      (node (ref "C53") (pin "1") (pintype "passive"))
      (node (ref "C54") (pin "1") (pinfunction "1_1") (pintype "passive"))
      (node (ref "C55") (pin "1") (pinfunction "1_1") (pintype "passive"))
      (node (ref "C56") (pin "1") (pinfunction "1_1") (pintype "passive"))
      (node (ref "C57") (pin "1") (pinfunction "1_1") (pintype "passive"))
      (node (ref "C58") (pin "1") (pinfunction "1_1") (pintype "passive"))
      (node (ref "C59") (pin "1") (pinfunction "1_1") (pintype "passive"))
      (node (ref "C6") (pin "1") (pinfunction "1_1") (pintype "passive"))
      (node (ref "C60") (pin "1") (pinfunction "1_1") (pintype "passive"))
      (node (ref "C61") (pin "1") (pinfunction "1_1") (pintype "passive"))
      (node (ref "C62") (pin "1") (pinfunction "1_1") (pintype "passive"))
      (node (ref "C63") (pin "2") (pinfunction "2_2") (pintype "passive"))
      (node (ref "C64") (pin "2") (pinfunction "2_2") (pintype "passive"))
      (node (ref "C65") (pin "1") (pinfunction "1_1") (pintype "passive"))
      (node (ref "C66") (pin "1") (pinfunction "1_1") (pintype "passive"))
      (node (ref "C67") (pin "1") (pinfunction "1_1") (pintype "passive"))
      (node (ref "C68") (pin "1") (pinfunction "1_1") (pintype "passive"))
      (node (ref "C69") (pin "1") (pinfunction "1_1") (pintype "passive"))
      (node (ref "C7") (pin "1") (pinfunction "1_1") (pintype "passive"))
      (node (ref "C73") (pin "2") (pinfunction "2_2") (pintype "passive"))
      (node (ref "C8") (pin "1") (pinfunction "1_1") (pintype "passive"))
      (node (ref "C9") (pin "1") (pinfunction "1_1") (pintype "passive"))
      (node (ref "D2") (pin "1") (pintype "passive"))
      (node (ref "DC_IN1") (pin "2") (pintype "passive"))
      (node (ref "DC_IN1") (pin "3") (pintype "passive"))
      (node (ref "EARTHNET1") (pin "13") (pinfunction "SHILED_13") (pintype "passive"))
      (node (ref "EARTHNET1") (pin "14") (pinfunction "SHILED_14") (pintype "passive"))
      (node (ref "EARTHNET1") (pin "8") (pinfunction "CHS_GND_8") (pintype "passive"))
      (node (ref "R1") (pin "1") (pinfunction "1_1") (pintype "passive"))
      (node (ref "R17") (pin "2") (pinfunction "2_2") (pintype "passive"))
      (node (ref "R34") (pin "2") (pinfunction "2_2") (pintype "passive"))
      (node (ref "R35") (pin "2") (pintype "passive"))
      (node (ref "R37") (pin "1") (pinfunction "1_1") (pintype "passive"))
      (node (ref "R38") (pin "2") (pinfunction "2_2") (pintype "passive"))
      (node (ref "R42") (pin "1") (pinfunction "1_1") (pintype "passive"))
      (node (ref "R45") (pin "1") (pinfunction "1_1") (pintype "passive"))
      (node (ref "R46") (pin "1") (pinfunction "1_1") (pintype "passive"))
      (node (ref "RESET1") (pin "2") (pinfunction "2_2") (pintype "passive"))
      (node (ref "TF1") (pin "10") (pinfunction "10_10") (pintype "passive"))
      (node (ref "TF1") (pin "11") (pinfunction "11_11") (pintype "passive"))
      (node (ref "TF1") (pin "12") (pinfunction "12_12") (pintype "passive"))
      (node (ref "TF1") (pin "13") (pinfunction "13_13") (pintype "passive"))
      (node (ref "TF1") (pin "6") (pinfunction "VSS_6") (pintype "passive"))
      (node (ref "TFTLCD1") (pin "22") (pinfunction "GND_22") (pintype "passive"))
      (node (ref "TFTLCD1") (pin "26") (pinfunction "GND_26") (pintype "passive"))
      (node (ref "TFTLCD1") (pin "27") (pinfunction "GND_27") (pintype "passive"))
      (node (ref "U1") (pin "12") (pinfunction "VSSQ1_12") (pintype "power_in"))
      (node (ref "U1") (pin "28") (pinfunction "VSS2_28") (pintype "power_in"))
      (node (ref "U1") (pin "41") (pinfunction "VSS0_41") (pintype "power_in"))
      (node (ref "U1") (pin "46") (pinfunction "VSSQ2_46") (pintype "power_in"))
      (node (ref "U1") (pin "52") (pinfunction "VSSQ3_52") (pintype "power_in"))
      (node (ref "U1") (pin "54") (pinfunction "VSS1_54") (pintype "power_in"))
      (node (ref "U1") (pin "6") (pinfunction "VSSQ0_6") (pintype "power_in"))
      (node (ref "U10") (pin "2") (pinfunction "2:_Cathod_2") (pintype "passive"))
      (node (ref "U11") (pin "2") (pinfunction "2:_Cathod_2") (pintype "passive"))
      (node (ref "U12") (pin "2") (pinfunction "GND_2") (pintype "passive"))
      (node (ref "U14") (pin "25") (pinfunction "GND_25") (pintype "passive"))
      (node (ref "U15") (pin "1") (pinfunction "GND_1") (pintype "power_in"))
      (node (ref "U16") (pin "2") (pinfunction "GND_2") (pintype "passive"))
      (node (ref "U17") (pin "4") (pinfunction "GND_4") (pintype "passive"))
      (node (ref "U18") (pin "1") (pinfunction "A0_1") (pintype "passive"))
      (node (ref "U18") (pin "2") (pinfunction "A1_2") (pintype "passive"))
      (node (ref "U18") (pin "3") (pinfunction "A2_3") (pintype "passive"))
      (node (ref "U18") (pin "4") (pinfunction "GND_4") (pintype "passive"))
      (node (ref "U18") (pin "7") (pinfunction "WP_7") (pintype "passive"))
      (node (ref "U19") (pin "2") (pinfunction "GND_2") (pintype "passive"))
      (node (ref "U2") (pin "107") (pinfunction "VSS_107") (pintype "power_in"))
      (node (ref "U2") (pin "120") (pinfunction "VSS_120") (pintype "power_in"))
      (node (ref "U2") (pin "130") (pinfunction "VSS_130") (pintype "power_in"))
      (node (ref "U2") (pin "16") (pinfunction "VSS_16") (pintype "power_in"))
      (node (ref "U2") (pin "31") (pinfunction "VSSA_31") (pintype "power_in"))
      (node (ref "U2") (pin "38") (pinfunction "VSS_38") (pintype "power_in"))
      (node (ref "U2") (pin "51") (pinfunction "VSS_51") (pintype "power_in"))
      (node (ref "U2") (pin "61") (pinfunction "VSS_61") (pintype "power_in"))
      (node (ref "U2") (pin "83") (pinfunction "VSS_83") (pintype "power_in"))
      (node (ref "U2") (pin "94") (pinfunction "VSS_94") (pintype "power_in"))
      (node (ref "U23") (pin "5") (pinfunction "GND_5") (pintype "passive"))
      (node (ref "U3") (pin "1") (pinfunction "GND_1") (pintype "passive"))
      (node (ref "U3") (pin "11") (pinfunction "GND_11") (pintype "passive"))
      (node (ref "U3") (pin "12") (pinfunction "GND_12") (pintype "passive"))
      (node (ref "U3") (pin "17") (pinfunction "GND_17") (pintype "passive"))
      (node (ref "U3") (pin "18") (pinfunction "GND_18") (pintype "passive"))
      (node (ref "U3") (pin "2") (pinfunction "GND_2") (pintype "passive"))
      (node (ref "U3") (pin "26") (pinfunction "GND_26") (pintype "passive"))
      (node (ref "U3") (pin "28") (pinfunction "GND_28") (pintype "passive"))
      (node (ref "U3") (pin "3") (pinfunction "GND_3") (pintype "passive"))
      (node (ref "U3") (pin "4") (pinfunction "GND_4") (pintype "passive"))
      (node (ref "U3") (pin "5") (pinfunction "GND_5") (pintype "passive"))
      (node (ref "U4") (pin "2") (pinfunction "2:_Cathod_2") (pintype "passive"))
      (node (ref "U5") (pin "2") (pinfunction "2:_Cathod_2") (pintype "passive"))
      (node (ref "U6") (pin "1") (pinfunction "GND_1") (pintype "passive"))
      (node (ref "U7") (pin "2") (pinfunction "2:_Cathod_2") (pintype "passive"))
      (node (ref "U9") (pin "2") (pinfunction "2:_Cathod_2") (pintype "passive"))
      (node (ref "USB1") (pin "5") (pinfunction "GND_5") (pintype "power_in"))
      (node (ref "Y2") (pin "2") (pinfunction "GND_2") (pintype "passive"))
      (node (ref "Y2") (pin "4") (pinfunction "GND_4") (pintype "passive"))
    )
    (net (code "128") (name "GND-AD") (class "Default")
      (node (ref "C70") (pin "2") (pinfunction "2_2") (pintype "passive"))
      (node (ref "C71") (pin "2") (pinfunction "2_2") (pintype "passive"))
      (node (ref "C72") (pin "2") (pinfunction "2_2") (pintype "passive"))
      (node (ref "C74") (pin "1") (pinfunction "1_1") (pintype "passive"))
      (node (ref "C75") (pin "1") (pinfunction "1_1") (pintype "passive"))
      (node (ref "C77") (pin "2") (pinfunction "2_2") (pintype "passive"))
      (node (ref "C78") (pin "1") (pinfunction "1_1") (pintype "passive"))
      (node (ref "C79") (pin "1") (pinfunction "1_1") (pintype "passive"))
      (node (ref "C80") (pin "2") (pinfunction "2_2") (pintype "passive"))
      (node (ref "C81") (pin "1") (pinfunction "1_1") (pintype "passive"))
      (node (ref "P1") (pin "1") (pinfunction "1_1") (pintype "passive"))
      (node (ref "P1") (pin "3") (pinfunction "3_3") (pintype "passive"))
      (node (ref "P3") (pin "1") (pinfunction "1_1") (pintype "passive"))
      (node (ref "P3") (pin "3") (pinfunction "3_3") (pintype "passive"))
      (node (ref "R57") (pin "2") (pinfunction "2_2") (pintype "passive"))
      (node (ref "U20") (pin "5") (pinfunction "GND_5") (pintype "passive"))
      (node (ref "U21") (pin "5") (pinfunction "GND_5") (pintype "passive"))
      (node (ref "U22") (pin "5") (pinfunction "GND_5") (pintype "passive"))
      (node (ref "U24") (pin "12") (pinfunction "AGND_12") (pintype "passive"))
      (node (ref "U24") (pin "2") (pinfunction "CH1_2") (pintype "passive"))
      (node (ref "U24") (pin "4") (pinfunction "CH3_4") (pintype "passive"))
      (node (ref "U24") (pin "7") (pinfunction "DGND_7") (pintype "passive"))
      (node (ref "U25") (pin "7") (pinfunction "0V_7") (pintype "passive"))
      (node (ref "U26") (pin "4") (pinfunction "GND_4") (pintype "passive"))
    )
    (net (code "129") (name "GND-Relay") (class "Default")
      (node (ref "C41") (pin "2") (pinfunction "2_2") (pintype "passive"))
      (node (ref "U13") (pin "7") (pinfunction "0V_7") (pintype "passive"))
      (node (ref "U8") (pin "9") (pinfunction "GND_9") (pintype "passive"))
    )
    (net (code "130") (name "Net-(BAT1-VCC)") (class "Default")
      (node (ref "BAT1") (pin "1") (pinfunction "VCC_1") (pintype "passive"))
      (node (ref "D1") (pin "2") (pintype "passive"))
    )
    (net (code "131") (name "Net-(BEEP1-P)") (class "Default")
      (node (ref "BEEP1") (pin "1") (pinfunction "P_1") (pintype "passive"))
      (node (ref "Q1") (pin "2") (pinfunction "2_2") (pintype "passive"))
    )
    (net (code "132") (name "Net-(D3-K)") (class "Default")
      (node (ref "D3") (pin "2") (pinfunction "K_2") (pintype "passive"))
      (node (ref "Q2") (pin "3") (pinfunction "C_3") (pintype "passive"))
      (node (ref "R27") (pin "1") (pinfunction "1_1") (pintype "passive"))
      (node (ref "R32") (pin "1") (pinfunction "1_1") (pintype "passive"))
    )
    (net (code "133") (name "Net-(D4-Pad1)") (class "Default")
      (node (ref "D4") (pin "1") (pintype "passive"))
      (node (ref "DC_IN1") (pin "1") (pintype "passive"))
    )
    (net (code "134") (name "Net-(EARTHNET1-LED(G)_K)") (class "Default")
      (node (ref "EARTHNET1") (pin "10") (pinfunction "LED(G)_K_10") (pintype "passive"))
      (node (ref "R45") (pin "2") (pinfunction "2_2") (pintype "passive"))
    )
    (net (code "135") (name "Net-(EARTHNET1-LED(Y)_K)") (class "Default")
      (node (ref "EARTHNET1") (pin "11") (pinfunction "LED(Y)_K_11") (pintype "passive"))
      (node (ref "R46") (pin "2") (pinfunction "2_2") (pintype "passive"))
    )
    (net (code "136") (name "Net-(P3-Pad2)") (class "Default")
      (node (ref "P3") (pin "2") (pinfunction "2_2") (pintype "passive"))
      (node (ref "R59") (pin "2") (pinfunction "2_2") (pintype "passive"))
    )
    (net (code "137") (name "Net-(P3-Pad4)") (class "Default")
      (node (ref "P3") (pin "4") (pinfunction "4_4") (pintype "passive"))
      (node (ref "R58") (pin "2") (pinfunction "2_2") (pintype "passive"))
    )
    (net (code "138") (name "Net-(Q1-Pad1)") (class "Default")
      (node (ref "Q1") (pin "1") (pinfunction "1_1") (pintype "passive"))
      (node (ref "R10") (pin "2") (pinfunction "2_2") (pintype "passive"))
    )
    (net (code "139") (name "Net-(Q2-B)") (class "Default")
      (node (ref "Q2") (pin "1") (pinfunction "B_1") (pintype "passive"))
      (node (ref "U15") (pin "14") (pinfunction "RTS#_14") (pintype "power_in"))
    )
    (net (code "140") (name "Net-(Q2-E)") (class "Default")
      (node (ref "Q2") (pin "2") (pinfunction "E_2") (pintype "passive"))
      (node (ref "R39") (pin "2") (pinfunction "2_2") (pintype "passive"))
    )
    (net (code "141") (name "Net-(Q3-B)") (class "Default")
      (node (ref "Q3") (pin "1") (pinfunction "B_1") (pintype "passive"))
      (node (ref "R39") (pin "1") (pinfunction "1_1") (pintype "passive"))
    )
    (net (code "142") (name "Net-(Q3-C)") (class "Default")
      (node (ref "Q3") (pin "3") (pinfunction "C_3") (pintype "passive"))
      (node (ref "R40") (pin "2") (pinfunction "2_2") (pintype "passive"))
    )
    (net (code "143") (name "Net-(U2A-PC14-OSC32_IN(PC14))") (class "Default")
      (node (ref "C14") (pin "2") (pinfunction "2_2") (pintype "passive"))
      (node (ref "U2") (pin "8") (pinfunction "PC14-OSC32_IN(PC14)_8") (pintype "bidirectional"))
      (node (ref "Y1") (pin "1") (pinfunction "OSC1_1") (pintype "passive"))
    )
    (net (code "144") (name "Net-(U2A-PC15-OSC32_OUT(PC15))") (class "Default")
      (node (ref "C15") (pin "2") (pinfunction "2_2") (pintype "passive"))
      (node (ref "U2") (pin "9") (pinfunction "PC15-OSC32_OUT(PC15)_9") (pintype "bidirectional"))
      (node (ref "Y1") (pin "2") (pinfunction "OSC2_2") (pintype "passive"))
    )
    (net (code "145") (name "Net-(U2B-PDR_ON)") (class "Default")
      (node (ref "R20") (pin "2") (pinfunction "2_2") (pintype "passive"))
      (node (ref "U2") (pin "143") (pinfunction "PDR_ON_143") (pintype "input"))
    )
    (net (code "146") (name "Net-(U2B-PH0-OSC_IN(PH0))") (class "Default")
      (node (ref "C28") (pin "2") (pinfunction "2_2") (pintype "passive"))
      (node (ref "U2") (pin "23") (pinfunction "PH0-OSC_IN(PH0)_23") (pintype "bidirectional"))
      (node (ref "Y2") (pin "3") (pinfunction "HOT_3") (pintype "passive"))
    )
    (net (code "147") (name "Net-(U2B-PH1-OSC_OUT(PH1))") (class "Default")
      (node (ref "C32") (pin "2") (pinfunction "2_2") (pintype "passive"))
      (node (ref "U2") (pin "24") (pinfunction "PH1-OSC_OUT(PH1)_24") (pintype "bidirectional"))
      (node (ref "Y2") (pin "1") (pinfunction "HOT_1") (pintype "passive"))
    )
    (net (code "148") (name "Net-(U2B-VCAP_1)") (class "Default")
      (node (ref "C33") (pin "2") (pinfunction "2_2") (pintype "passive"))
      (node (ref "U2") (pin "71") (pinfunction "VCAP_1_71") (pintype "power_in"))
    )
    (net (code "149") (name "Net-(U2B-VCAP_2)") (class "Default")
      (node (ref "C34") (pin "2") (pinfunction "2_2") (pintype "passive"))
      (node (ref "U2") (pin "106") (pinfunction "VCAP_2_106") (pintype "power_in"))
    )
    (net (code "150") (name "Net-(U2C-VBAT)") (class "Default")
      (node (ref "C3") (pin "2") (pinfunction "2_2") (pintype "passive"))
      (node (ref "D1") (pin "3") (pintype "passive"))
      (node (ref "U2") (pin "6") (pinfunction "VBAT_6") (pintype "power_in"))
    )
    (net (code "151") (name "Net-(U2C-VDDA)") (class "Default")
      (node (ref "C5") (pin "2") (pinfunction "2_2") (pintype "passive"))
      (node (ref "C6") (pin "2") (pinfunction "2_2") (pintype "passive"))
      (node (ref "R9") (pin "2") (pinfunction "2_2") (pintype "passive"))
      (node (ref "U2") (pin "33") (pinfunction "VDDA_33") (pintype "power_in"))
    )
    (net (code "152") (name "Net-(U2C-VREF+)") (class "Default")
      (node (ref "C1") (pin "2") (pinfunction "2_2") (pintype "passive"))
      (node (ref "R7") (pin "1") (pinfunction "1_1") (pintype "passive"))
      (node (ref "U2") (pin "32") (pinfunction "VREF+_32") (pintype "power_in"))
    )
    (net (code "153") (name "Net-(U4-1:_Anode)") (class "Default")
      (node (ref "R11") (pin "2") (pinfunction "2_2") (pintype "passive"))
      (node (ref "U4") (pin "1") (pinfunction "1:_Anode_1") (pintype "passive"))
    )
    (net (code "154") (name "Net-(U4-3:_Emitter)") (class "Default")
      (node (ref "U4") (pin "3") (pinfunction "3:_Emitter_3") (pintype "passive"))
      (node (ref "U8") (pin "1") (pinfunction "IN1_1") (pintype "passive"))
    )
    (net (code "155") (name "Net-(U4-4:_Collector)") (class "Default")
      (node (ref "R12") (pin "1") (pinfunction "1_1") (pintype "passive"))
      (node (ref "U4") (pin "4") (pinfunction "4:_Collector_4") (pintype "passive"))
    )
    (net (code "156") (name "Net-(U5-1:_Anode)") (class "Default")
      (node (ref "R13") (pin "2") (pinfunction "2_2") (pintype "passive"))
      (node (ref "U5") (pin "1") (pinfunction "1:_Anode_1") (pintype "passive"))
    )
    (net (code "157") (name "Net-(U5-3:_Emitter)") (class "Default")
      (node (ref "U5") (pin "3") (pinfunction "3:_Emitter_3") (pintype "passive"))
      (node (ref "U8") (pin "2") (pinfunction "IN2_2") (pintype "passive"))
    )
    (net (code "158") (name "Net-(U5-4:_Collector)") (class "Default")
      (node (ref "R14") (pin "1") (pinfunction "1_1") (pintype "passive"))
      (node (ref "U5") (pin "4") (pinfunction "4:_Collector_4") (pintype "passive"))
    )
    (net (code "159") (name "Net-(U7-1:_Anode)") (class "Default")
      (node (ref "R15") (pin "2") (pinfunction "2_2") (pintype "passive"))
      (node (ref "U7") (pin "1") (pinfunction "1:_Anode_1") (pintype "passive"))
    )
    (net (code "160") (name "Net-(U7-3:_Emitter)") (class "Default")
      (node (ref "U7") (pin "3") (pinfunction "3:_Emitter_3") (pintype "passive"))
      (node (ref "U8") (pin "3") (pinfunction "IN3_3") (pintype "passive"))
    )
    (net (code "161") (name "Net-(U7-4:_Collector)") (class "Default")
      (node (ref "R16") (pin "1") (pinfunction "1_1") (pintype "passive"))
      (node (ref "U7") (pin "4") (pinfunction "4:_Collector_4") (pintype "passive"))
    )
    (net (code "162") (name "Net-(U8-IN4)") (class "Default")
      (node (ref "U8") (pin "4") (pinfunction "IN4_4") (pintype "passive"))
      (node (ref "U9") (pin "3") (pinfunction "3:_Emitter_3") (pintype "passive"))
    )
    (net (code "163") (name "Net-(U8-OUT1)") (class "Default")
      (node (ref "HF1") (pin "1") (pintype "passive"))
      (node (ref "U8") (pin "18") (pinfunction "OUT1_18") (pintype "passive"))
    )
    (net (code "164") (name "Net-(U8-OUT2)") (class "Default")
      (node (ref "HF2") (pin "1") (pintype "passive"))
      (node (ref "U8") (pin "17") (pinfunction "OUT2_17") (pintype "passive"))
    )
    (net (code "165") (name "Net-(U8-OUT3)") (class "Default")
      (node (ref "HF3") (pin "1") (pintype "passive"))
      (node (ref "U8") (pin "16") (pinfunction "OUT3_16") (pintype "passive"))
    )
    (net (code "166") (name "Net-(U8-OUT4)") (class "Default")
      (node (ref "HF4") (pin "1") (pintype "passive"))
      (node (ref "U8") (pin "15") (pinfunction "OUT4_15") (pintype "passive"))
    )
    (net (code "167") (name "Net-(U8-OUT5)") (class "Default")
      (node (ref "HF5") (pin "1") (pintype "passive"))
      (node (ref "U8") (pin "14") (pinfunction "OUT5_14") (pintype "passive"))
    )
    (net (code "168") (name "Net-(U8-OUT6)") (class "Default")
      (node (ref "HF6") (pin "1") (pintype "passive"))
      (node (ref "U8") (pin "13") (pinfunction "OUT6_13") (pintype "passive"))
    )
    (net (code "169") (name "Net-(U9-1:_Anode)") (class "Default")
      (node (ref "R18") (pin "2") (pinfunction "2_2") (pintype "passive"))
      (node (ref "U9") (pin "1") (pinfunction "1:_Anode_1") (pintype "passive"))
    )
    (net (code "170") (name "Net-(U9-4:_Collector)") (class "Default")
      (node (ref "R19") (pin "1") (pinfunction "1_1") (pintype "passive"))
      (node (ref "U9") (pin "4") (pinfunction "4:_Collector_4") (pintype "passive"))
    )
    (net (code "171") (name "Net-(U10-1:_Anode)") (class "Default")
      (node (ref "R22") (pin "2") (pinfunction "2_2") (pintype "passive"))
      (node (ref "U10") (pin "1") (pinfunction "1:_Anode_1") (pintype "passive"))
    )
    (net (code "172") (name "Net-(U10-3:_Emitter)") (class "Default")
      (node (ref "U10") (pin "3") (pinfunction "3:_Emitter_3") (pintype "passive"))
      (node (ref "U8") (pin "5") (pinfunction "IN5_5") (pintype "passive"))
    )
    (net (code "173") (name "Net-(U10-4:_Collector)") (class "Default")
      (node (ref "R23") (pin "1") (pinfunction "1_1") (pintype "passive"))
      (node (ref "U10") (pin "4") (pinfunction "4:_Collector_4") (pintype "passive"))
    )
    (net (code "174") (name "Net-(U11-1:_Anode)") (class "Default")
      (node (ref "R24") (pin "2") (pinfunction "2_2") (pintype "passive"))
      (node (ref "U11") (pin "1") (pinfunction "1:_Anode_1") (pintype "passive"))
    )
    (net (code "175") (name "Net-(U11-3:_Emitter)") (class "Default")
      (node (ref "U11") (pin "3") (pinfunction "3:_Emitter_3") (pintype "passive"))
      (node (ref "U8") (pin "6") (pinfunction "IN6_6") (pintype "passive"))
    )
    (net (code "176") (name "Net-(U11-4:_Collector)") (class "Default")
      (node (ref "R25") (pin "1") (pinfunction "1_1") (pintype "passive"))
      (node (ref "U11") (pin "4") (pinfunction "4:_Collector_4") (pintype "passive"))
    )
    (net (code "177") (name "Net-(U12-BYP)") (class "Default")
      (node (ref "C37") (pin "2") (pinfunction "2_2") (pintype "passive"))
      (node (ref "U12") (pin "4") (pinfunction "BYP_4") (pintype "passive"))
    )
    (net (code "178") (name "Net-(U12-CE)") (class "Default")
      (node (ref "C36") (pin "2") (pinfunction "2_2") (pintype "passive"))
      (node (ref "F1") (pin "2") (pinfunction "2_2") (pintype "passive"))
      (node (ref "U12") (pin "1") (pinfunction "VIN_1") (pintype "passive"))
      (node (ref "U12") (pin "3") (pinfunction "CE_3") (pintype "passive"))
    )
    (net (code "179") (name "Net-(U14-MDIO)") (class "Default")
      (node (ref "R28") (pin "2") (pinfunction "2_2") (pintype "passive"))
      (node (ref "U14") (pin "12") (pinfunction "MDIO_12") (pintype "passive"))
    )
    (net (code "180") (name "Net-(U14-RBIAS)") (class "Default")
      (node (ref "R42") (pin "2") (pinfunction "2_2") (pintype "passive"))
      (node (ref "U14") (pin "24") (pinfunction "RBIAS_24") (pintype "passive"))
    )
    (net (code "181") (name "Net-(U14-VDDCR)") (class "Default")
      (node (ref "C54") (pin "2") (pinfunction "2_2") (pintype "passive"))
      (node (ref "C55") (pin "2") (pinfunction "2_2") (pintype "passive"))
      (node (ref "U14") (pin "6") (pinfunction "VDDCR_6") (pintype "passive"))
    )
    (net (code "182") (name "Net-(U14-XTAL1{slash}CLKIN)") (class "Default")
      (node (ref "C60") (pin "2") (pinfunction "2_2") (pintype "passive"))
      (node (ref "R43") (pin "2") (pinfunction "2_2") (pintype "passive"))
      (node (ref "U14") (pin "5") (pinfunction "XTAL1/CLKIN_5") (pintype "passive"))
      (node (ref "Y4") (pin "2") (pinfunction "OSC2_2") (pintype "passive"))
    )
    (net (code "183") (name "Net-(U14-XTAL2)") (class "Default")
      (node (ref "C59") (pin "2") (pinfunction "2_2") (pintype "passive"))
      (node (ref "R43") (pin "1") (pinfunction "1_1") (pintype "passive"))
      (node (ref "U14") (pin "4") (pinfunction "XTAL2_4") (pintype "passive"))
      (node (ref "Y4") (pin "1") (pinfunction "OSC1_1") (pintype "passive"))
    )
    (net (code "184") (name "Net-(U15-DTR#)") (class "Default")
      (node (ref "R32") (pin "2") (pinfunction "2_2") (pintype "passive"))
      (node (ref "U15") (pin "13") (pinfunction "DTR#_13") (pintype "power_in"))
    )
    (net (code "185") (name "Net-(U15-V3)") (class "Default")
      (node (ref "C47") (pin "1") (pintype "passive"))
      (node (ref "U15") (pin "4") (pinfunction "V3_4") (pintype "power_in"))
    )
    (net (code "186") (name "Net-(U15-XI)") (class "Default")
      (node (ref "C49") (pin "2") (pintype "passive"))
      (node (ref "U15") (pin "7") (pinfunction "XI_7") (pintype "power_in"))
      (node (ref "Y3") (pin "1") (pinfunction "OSC1_1") (pintype "passive"))
    )
    (net (code "187") (name "Net-(U15-XO)") (class "Default")
      (node (ref "C52") (pin "2") (pintype "passive"))
      (node (ref "U15") (pin "8") (pinfunction "XO_8") (pintype "power_in"))
      (node (ref "Y3") (pin "2") (pinfunction "OSC2_2") (pintype "passive"))
    )
    (net (code "188") (name "Net-(U16-BST)") (class "Default")
      (node (ref "C42") (pin "2") (pintype "passive"))
      (node (ref "U16") (pin "1") (pinfunction "BST_1") (pintype "passive"))
    )
    (net (code "189") (name "Net-(U16-EN)") (class "Default")
      (node (ref "R36") (pin "2") (pintype "passive"))
      (node (ref "U16") (pin "4") (pinfunction "EN_4") (pintype "passive"))
    )
    (net (code "190") (name "Net-(U16-FB)") (class "Default")
      (node (ref "R35") (pin "1") (pintype "passive"))
      (node (ref "R41") (pin "2") (pintype "passive"))
      (node (ref "U16") (pin "3") (pinfunction "FB_3") (pintype "passive"))
    )
    (net (code "191") (name "Net-(U16-IN)") (class "Default")
      (node (ref "C51") (pin "2") (pintype "passive"))
      (node (ref "C53") (pin "2") (pintype "passive"))
      (node (ref "D4") (pin "2") (pintype "passive"))
      (node (ref "R36") (pin "1") (pintype "passive"))
      (node (ref "U16") (pin "5") (pinfunction "IN_5") (pintype "passive"))
    )
    (net (code "192") (name "Net-(U16-SW)") (class "Default")
      (node (ref "C42") (pin "1") (pintype "passive"))
      (node (ref "D2") (pin "2") (pintype "passive"))
      (node (ref "L1") (pin "2") (pinfunction "2_2") (pintype "passive"))
      (node (ref "U16") (pin "6") (pinfunction "SW_6") (pintype "passive"))
    )
    (net (code "193") (name "Net-(U20-IN+)") (class "Default")
      (node (ref "R26") (pin "2") (pinfunction "2_2") (pintype "passive"))
      (node (ref "U20") (pin "2") (pinfunction "IN+_2") (pintype "passive"))
    )
    (net (code "194") (name "Net-(U21-IN+)") (class "Default")
      (node (ref "R49") (pin "2") (pinfunction "2_2") (pintype "passive"))
      (node (ref "U21") (pin "2") (pinfunction "IN+_2") (pintype "passive"))
    )
    (net (code "195") (name "Net-(U22-IN+)") (class "Default")
      (node (ref "R51") (pin "2") (pinfunction "2_2") (pintype "passive"))
      (node (ref "U22") (pin "2") (pinfunction "IN+_2") (pintype "passive"))
    )
    (net (code "196") (name "Net-(U23-IN+)") (class "Default")
      (node (ref "R53") (pin "2") (pinfunction "2_2") (pintype "passive"))
      (node (ref "U23") (pin "2") (pinfunction "IN+_2") (pintype "passive"))
    )
    (net (code "197") (name "Net-(U24-CH0)") (class "Default")
      (node (ref "C74") (pin "2") (pinfunction "2_2") (pintype "passive"))
      (node (ref "R55") (pin "2") (pinfunction "2_2") (pintype "passive"))
      (node (ref "U24") (pin "1") (pinfunction "CH0_1") (pintype "passive"))
    )
    (net (code "198") (name "Net-(U24-CH2)") (class "Default")
      (node (ref "C75") (pin "2") (pinfunction "2_2") (pintype "passive"))
      (node (ref "R56") (pin "2") (pinfunction "2_2") (pintype "passive"))
      (node (ref "U24") (pin "3") (pinfunction "CH2_3") (pintype "passive"))
    )
    (net (code "199") (name "REF-4.096V") (class "Default")
      (node (ref "C80") (pin "1") (pinfunction "1_1") (pintype "passive"))
      (node (ref "C81") (pin "2") (pinfunction "2_2") (pintype "passive"))
      (node (ref "U24") (pin "13") (pinfunction "Vref_13") (pintype "passive"))
      (node (ref "U26") (pin "6") (pinfunction "OUT_6") (pintype "passive"))
    )
    (net (code "200") (name "VBTN") (class "Default")
      (node (ref "C43") (pin "2") (pintype "passive"))
      (node (ref "C44") (pin "2") (pintype "passive"))
      (node (ref "C45") (pin "2") (pintype "passive"))
      (node (ref "C46") (pin "1") (pinfunction "VCC_1") (pintype "passive"))
      (node (ref "K1") (pin "3") (pinfunction "I/O1_3") (pintype "passive"))
      (node (ref "L1") (pin "1") (pinfunction "1_1") (pintype "passive"))
      (node (ref "R41") (pin "1") (pintype "passive"))
      (node (ref "U15") (pin "16") (pinfunction "VCC_16") (pintype "power_in"))
      (node (ref "USB1") (pin "1") (pinfunction "VCC_1") (pintype "power_in"))
    )
    (net (code "201") (name "VCC-1") (class "Default")
      (node (ref "C10") (pin "2") (pinfunction "2_2") (pintype "passive"))
      (node (ref "C11") (pin "2") (pinfunction "2_2") (pintype "passive"))
      (node (ref "C12") (pin "2") (pinfunction "2_2") (pintype "passive"))
      (node (ref "C13") (pin "2") (pinfunction "2_2") (pintype "passive"))
      (node (ref "C16") (pin "2") (pinfunction "2_2") (pintype "passive"))
      (node (ref "C17") (pin "2") (pinfunction "2_2") (pintype "passive"))
      (node (ref "C18") (pin "2") (pinfunction "2_2") (pintype "passive"))
      (node (ref "C19") (pin "2") (pinfunction "2_2") (pintype "passive"))
      (node (ref "C20") (pin "2") (pinfunction "2_2") (pintype "passive"))
      (node (ref "C21") (pin "2") (pinfunction "2_2") (pintype "passive"))
      (node (ref "C22") (pin "2") (pinfunction "2_2") (pintype "passive"))
      (node (ref "C23") (pin "2") (pinfunction "2_2") (pintype "passive"))
      (node (ref "C24") (pin "2") (pinfunction "2_2") (pintype "passive"))
      (node (ref "C25") (pin "2") (pinfunction "2_2") (pintype "passive"))
      (node (ref "C26") (pin "2") (pinfunction "2_2") (pintype "passive"))
      (node (ref "C27") (pin "2") (pinfunction "2_2") (pintype "passive"))
      (node (ref "C38") (pin "2") (pinfunction "2_2") (pintype "passive"))
      (node (ref "C39") (pin "2") (pinfunction "2_2") (pintype "passive"))
      (node (ref "C63") (pin "1") (pinfunction "1_1") (pintype "passive"))
      (node (ref "C64") (pin "1") (pinfunction "1_1") (pintype "passive"))
      (node (ref "C7") (pin "2") (pinfunction "2_2") (pintype "passive"))
      (node (ref "C8") (pin "2") (pinfunction "2_2") (pintype "passive"))
      (node (ref "C9") (pin "2") (pinfunction "2_2") (pintype "passive"))
      (node (ref "D1") (pin "1") (pintype "passive"))
      (node (ref "Q3") (pin "2") (pinfunction "E_2") (pintype "passive"))
      (node (ref "R20") (pin "1") (pinfunction "1_1") (pintype "passive"))
      (node (ref "R21") (pin "2") (pinfunction "2_2") (pintype "passive"))
      (node (ref "R27") (pin "2") (pinfunction "2_2") (pintype "passive"))
      (node (ref "R44") (pin "2") (pinfunction "2_2") (pintype "passive"))
      (node (ref "R47") (pin "2") (pinfunction "2_2") (pintype "passive"))
      (node (ref "R7") (pin "2") (pinfunction "2_2") (pintype "passive"))
      (node (ref "R8") (pin "1") (pinfunction "1_1") (pintype "passive"))
      (node (ref "R9") (pin "1") (pinfunction "1_1") (pintype "passive"))
      (node (ref "U1") (pin "1") (pinfunction "VDD0_1") (pintype "power_in"))
      (node (ref "U1") (pin "14") (pinfunction "VDD1_14") (pintype "power_in"))
      (node (ref "U1") (pin "27") (pinfunction "VDD2_27") (pintype "power_in"))
      (node (ref "U1") (pin "3") (pinfunction "VDDQ0_3") (pintype "power_in"))
      (node (ref "U1") (pin "43") (pinfunction "VDDQ2_43") (pintype "power_in"))
      (node (ref "U1") (pin "49") (pinfunction "VDDQ3_49") (pintype "power_in"))
      (node (ref "U1") (pin "9") (pinfunction "VDDQ1_9") (pintype "power_in"))
      (node (ref "U12") (pin "5") (pinfunction "OUT_5") (pintype "passive"))
      (node (ref "U17") (pin "3") (pinfunction "~{WP}(IO2)_3") (pintype "passive"))
      (node (ref "U17") (pin "7") (pinfunction "HOLD/RST(IO3)_7") (pintype "power_in"))
      (node (ref "U17") (pin "8") (pinfunction "VCC_8") (pintype "passive"))
      (node (ref "U18") (pin "8") (pinfunction "VCC1_8") (pintype "passive"))
      (node (ref "U2") (pin "108") (pinfunction "VDD_108") (pintype "power_in"))
      (node (ref "U2") (pin "121") (pinfunction "VDD_121") (pintype "power_in"))
      (node (ref "U2") (pin "131") (pinfunction "VDD_131") (pintype "power_in"))
      (node (ref "U2") (pin "144") (pinfunction "VDD_144") (pintype "power_in"))
      (node (ref "U2") (pin "17") (pinfunction "VDD_17") (pintype "power_in"))
      (node (ref "U2") (pin "30") (pinfunction "VDD_30") (pintype "power_in"))
      (node (ref "U2") (pin "39") (pinfunction "VDD_39") (pintype "power_in"))
      (node (ref "U2") (pin "52") (pinfunction "VDD_52") (pintype "power_in"))
      (node (ref "U2") (pin "62") (pinfunction "VDD_62") (pintype "power_in"))
      (node (ref "U2") (pin "72") (pinfunction "VDD_72") (pintype "power_in"))
      (node (ref "U2") (pin "84") (pinfunction "VDD_84") (pintype "power_in"))
      (node (ref "U2") (pin "95") (pinfunction "VDD_95") (pintype "power_in"))
    )
    (net (code "202") (name "VCC-2") (class "Default")
      (node (ref "C30") (pin "1") (pinfunction "VCC_1") (pintype "passive"))
      (node (ref "C31") (pin "2") (pinfunction "2_2") (pintype "passive"))
      (node (ref "C4") (pin "2") (pinfunction "2_2") (pintype "passive"))
      (node (ref "C48") (pin "1") (pinfunction "1_1") (pintype "passive"))
      (node (ref "C56") (pin "2") (pinfunction "2_2") (pintype "passive"))
      (node (ref "C61") (pin "2") (pinfunction "2_2") (pintype "passive"))
      (node (ref "C73") (pin "1") (pinfunction "1_1") (pintype "passive"))
      (node (ref "L2") (pin "1") (pinfunction "1_1") (pintype "passive"))
      (node (ref "Q1") (pin "3") (pinfunction "3_3") (pintype "passive"))
      (node (ref "R2") (pin "2") (pinfunction "2_2") (pintype "passive"))
      (node (ref "R26") (pin "1") (pinfunction "1_1") (pintype "passive"))
      (node (ref "R3") (pin "2") (pinfunction "2_2") (pintype "passive"))
      (node (ref "R4") (pin "2") (pinfunction "2_2") (pintype "passive"))
      (node (ref "R49") (pin "1") (pinfunction "1_1") (pintype "passive"))
      (node (ref "R5") (pin "2") (pinfunction "2_2") (pintype "passive"))
      (node (ref "R51") (pin "1") (pinfunction "1_1") (pintype "passive"))
      (node (ref "R54") (pin "2") (pinfunction "2_2") (pintype "passive"))
      (node (ref "R6") (pin "2") (pinfunction "2_2") (pintype "passive"))
      (node (ref "TF1") (pin "4") (pinfunction "VDD_4") (pintype "passive"))
      (node (ref "TFTLCD1") (pin "24") (pinfunction "VDD3.3_24") (pintype "passive"))
      (node (ref "TFTLCD1") (pin "25") (pinfunction "VDD3.3_25") (pintype "passive"))
      (node (ref "U14") (pin "9") (pinfunction "VDDIO_9") (pintype "passive"))
      (node (ref "U19") (pin "3") (pinfunction "PWR_3") (pintype "passive"))
      (node (ref "U19") (pin "4") (pinfunction "3.3V_4") (pintype "passive"))
      (node (ref "U23") (pin "7") (pinfunction "EN_7") (pintype "passive"))
      (node (ref "U23") (pin "8") (pinfunction "VCC_8") (pintype "passive"))
      (node (ref "U6") (pin "2") (pinfunction "OUT_2") (pintype "passive"))
      (node (ref "U6") (pin "4") (pinfunction "OUT_4") (pintype "passive"))
    )
    (net (code "203") (name "VCC-5") (class "Default")
      (node (ref "C2") (pin "2") (pintype "passive"))
      (node (ref "C29") (pin "2") (pinfunction "2_2") (pintype "passive"))
      (node (ref "C50") (pin "1") (pinfunction "1_1") (pintype "passive"))
      (node (ref "C76") (pin "1") (pinfunction "1_1") (pintype "passive"))
      (node (ref "F1") (pin "1") (pinfunction "1_1") (pintype "passive"))
      (node (ref "K1") (pin "2") (pinfunction "TAP1_2") (pintype "passive"))
      (node (ref "TFTLCD1") (pin "28") (pinfunction "BL_VDD_28") (pintype "passive"))
      (node (ref "U19") (pin "1") (pinfunction "VCC_1") (pintype "passive"))
      (node (ref "U25") (pin "4") (pinfunction "Vin_4") (pintype "passive"))
      (node (ref "U3") (pin "10") (pinfunction "VCC_10") (pintype "passive"))
      (node (ref "U3") (pin "9") (pinfunction "VCC_9") (pintype "passive"))
      (node (ref "U6") (pin "3") (pinfunction "IN_3") (pintype "passive"))
    )
    (net (code "204") (name "VCC-E") (class "Default")
      (node (ref "C57") (pin "2") (pinfunction "2_2") (pintype "passive"))
      (node (ref "C58") (pin "2") (pinfunction "2_2") (pintype "passive"))
      (node (ref "C62") (pin "2") (pinfunction "2_2") (pintype "passive"))
      (node (ref "C65") (pin "2") (pinfunction "2_2") (pintype "passive"))
      (node (ref "EARTHNET1") (pin "4") (pinfunction "TCT_4") (pintype "passive"))
      (node (ref "EARTHNET1") (pin "5") (pinfunction "RCT_5") (pintype "passive"))
      (node (ref "L2") (pin "2") (pinfunction "2_2") (pintype "passive"))
      (node (ref "R29") (pin "2") (pinfunction "2_2") (pintype "passive"))
      (node (ref "R30") (pin "2") (pinfunction "2_2") (pintype "passive"))
      (node (ref "R31") (pin "2") (pinfunction "2_2") (pintype "passive"))
      (node (ref "R33") (pin "2") (pinfunction "2_2") (pintype "passive"))
      (node (ref "U14") (pin "1") (pinfunction "VDD2A_1") (pintype "passive"))
      (node (ref "U14") (pin "19") (pinfunction "VDD1A_19") (pintype "passive"))
    )
    (net (code "205") (name "unconnected-(EARTHNET1-NC-Pad7)") (class "Default")
      (node (ref "EARTHNET1") (pin "7") (pinfunction "NC_7") (pintype "passive+no_connect"))
    )
    (net (code "206") (name "unconnected-(K1-I{slash}O1-Pad1)") (class "Default")
      (node (ref "K1") (pin "1") (pinfunction "I/O1_1") (pintype "passive"))
    )
    (net (code "207") (name "unconnected-(K1-I{slash}O2-Pad4)") (class "Default")
      (node (ref "K1") (pin "4") (pinfunction "I/O2_4") (pintype "passive"))
    )
    (net (code "208") (name "unconnected-(K1-I{slash}O2-Pad6)") (class "Default")
      (node (ref "K1") (pin "6") (pinfunction "I/O2_6") (pintype "passive"))
    )
    (net (code "209") (name "unconnected-(K1-TAP2-Pad5)") (class "Default")
      (node (ref "K1") (pin "5") (pinfunction "TAP2_5") (pintype "passive"))
    )
    (net (code "210") (name "unconnected-(TF1-Pad9)") (class "Default")
      (node (ref "TF1") (pin "9") (pinfunction "9_9") (pintype "passive+no_connect"))
    )
    (net (code "211") (name "unconnected-(TF1-Pad14)") (class "Default")
      (node (ref "TF1") (pin "14") (pinfunction "14_14") (pintype "passive+no_connect"))
    )
    (net (code "212") (name "unconnected-(TF1-Pad15)") (class "Default")
      (node (ref "TF1") (pin "15") (pinfunction "15_15") (pintype "passive+no_connect"))
    )
    (net (code "213") (name "unconnected-(TFTLCD1-MISO-Pad29)") (class "Default")
      (node (ref "TFTLCD1") (pin "29") (pinfunction "MISO_29") (pintype "passive"))
    )
    (net (code "214") (name "unconnected-(TFTLCD1-MO-Pad32)") (class "Default")
      (node (ref "TFTLCD1") (pin "32") (pinfunction "MO_32") (pintype "passive+no_connect"))
    )
    (net (code "215") (name "unconnected-(U2A-PA0-WKUP(PA0)-Pad34)") (class "Default")
      (node (ref "U2") (pin "34") (pinfunction "PA0-WKUP(PA0)_34") (pintype "bidirectional"))
    )
    (net (code "216") (name "unconnected-(U2A-PA3-Pad37)") (class "Default")
      (node (ref "U2") (pin "37") (pinfunction "PA3_37") (pintype "bidirectional"))
    )
    (net (code "217") (name "unconnected-(U2A-PA13(JTMS-SWDIO)-Pad105)") (class "Default")
      (node (ref "U2") (pin "105") (pinfunction "PA13(JTMS-SWDIO)_105") (pintype "bidirectional"))
    )
    (net (code "218") (name "unconnected-(U2A-PA14(JTCK-SWCLK)-Pad109)") (class "Default")
      (node (ref "U2") (pin "109") (pinfunction "PA14(JTCK-SWCLK)_109") (pintype "bidirectional"))
    )
    (net (code "219") (name "unconnected-(U2A-PB10-Pad69)") (class "Default")
      (node (ref "U2") (pin "69") (pinfunction "PB10_69") (pintype "bidirectional"))
    )
    (net (code "220") (name "unconnected-(U2A-PB14-Pad75)") (class "Default")
      (node (ref "U2") (pin "75") (pinfunction "PB14_75") (pintype "bidirectional"))
    )
    (net (code "221") (name "unconnected-(U2A-PC6-Pad96)") (class "Default")
      (node (ref "U2") (pin "96") (pinfunction "PC6_96") (pintype "bidirectional"))
    )
    (net (code "222") (name "unconnected-(U2A-PC7-Pad97)") (class "Default")
      (node (ref "U2") (pin "97") (pinfunction "PC7_97") (pintype "bidirectional"))
    )
    (net (code "223") (name "unconnected-(U2A-PC13-Pad7)") (class "Default")
      (node (ref "U2") (pin "7") (pinfunction "PC13_7") (pintype "bidirectional"))
    )
    (net (code "224") (name "unconnected-(U2A-PD3-Pad117)") (class "Default")
      (node (ref "U2") (pin "117") (pinfunction "PD3_117") (pintype "bidirectional"))
    )
    (net (code "225") (name "unconnected-(U2B-PE2-Pad1)") (class "Default")
      (node (ref "U2") (pin "1") (pinfunction "PE2_1") (pintype "bidirectional"))
    )
    (net (code "226") (name "unconnected-(U2B-PE3-Pad2)") (class "Default")
      (node (ref "U2") (pin "2") (pinfunction "PE3_2") (pintype "bidirectional"))
    )
    (net (code "227") (name "unconnected-(U2B-PE4-Pad3)") (class "Default")
      (node (ref "U2") (pin "3") (pinfunction "PE4_3") (pintype "bidirectional"))
    )
    (net (code "228") (name "unconnected-(U2B-PE5-Pad4)") (class "Default")
      (node (ref "U2") (pin "4") (pinfunction "PE5_4") (pintype "bidirectional"))
    )
    (net (code "229") (name "unconnected-(U2B-PE6-Pad5)") (class "Default")
      (node (ref "U2") (pin "5") (pinfunction "PE6_5") (pintype "bidirectional"))
    )
    (net (code "230") (name "unconnected-(U2B-PF10-Pad22)") (class "Default")
      (node (ref "U2") (pin "22") (pinfunction "PF10_22") (pintype "bidirectional"))
    )
    (net (code "231") (name "unconnected-(U2B-PG7-Pad92)") (class "Default")
      (node (ref "U2") (pin "92") (pinfunction "PG7_92") (pintype "bidirectional"))
    )
    (net (code "232") (name "unconnected-(U3-ANT-Pad27)") (class "Default")
      (node (ref "U3") (pin "27") (pinfunction "ANT_27") (pintype "passive"))
    )
    (net (code "233") (name "unconnected-(U3-DI02-Pad8)") (class "Default")
      (node (ref "U3") (pin "8") (pinfunction "DI02_8") (pintype "passive"))
    )
    (net (code "234") (name "unconnected-(U3-DIO0-Pad20)") (class "Default")
      (node (ref "U3") (pin "20") (pinfunction "DIO0_20") (pintype "passive"))
    )
    (net (code "235") (name "unconnected-(U3-DIO1-Pad19)") (class "Default")
      (node (ref "U3") (pin "19") (pinfunction "DIO1_19") (pintype "passive"))
    )
    (net (code "236") (name "unconnected-(U3-DIO3-Pad14)") (class "Default")
      (node (ref "U3") (pin "14") (pinfunction "DIO3_14") (pintype "passive"))
    )
    (net (code "237") (name "unconnected-(U3-DIO4-Pad15)") (class "Default")
      (node (ref "U3") (pin "15") (pinfunction "DIO4_15") (pintype "passive"))
    )
    (net (code "238") (name "unconnected-(U3-DIO5-Pad16)") (class "Default")
      (node (ref "U3") (pin "16") (pinfunction "DIO5_16") (pintype "passive"))
    )
    (net (code "239") (name "unconnected-(U3-NC-Pad13)") (class "Default")
      (node (ref "U3") (pin "13") (pinfunction "NC_13") (pintype "passive"))
    )
    (net (code "240") (name "unconnected-(U8-IN7-Pad7)") (class "Default")
      (node (ref "U8") (pin "7") (pinfunction "IN7_7") (pintype "passive"))
    )
    (net (code "241") (name "unconnected-(U8-IN8-Pad8)") (class "Default")
      (node (ref "U8") (pin "8") (pinfunction "IN8_8") (pintype "passive+no_connect"))
    )
    (net (code "242") (name "unconnected-(U8-OUT7-Pad12)") (class "Default")
      (node (ref "U8") (pin "12") (pinfunction "OUT7_12") (pintype "passive+no_connect"))
    )
    (net (code "243") (name "unconnected-(U8-OUT8-Pad11)") (class "Default")
      (node (ref "U8") (pin "11") (pinfunction "OUT8_11") (pintype "passive+no_connect"))
    )
    (net (code "244") (name "unconnected-(U14-RXER{slash}PHYAD0-Pad10)") (class "Default")
      (node (ref "U14") (pin "10") (pinfunction "RXER/PHYAD0_10") (pintype "passive"))
    )
    (net (code "245") (name "unconnected-(U15-CTS#-Pad9)") (class "Default")
      (node (ref "U15") (pin "9") (pinfunction "CTS#_9") (pintype "power_in+no_connect"))
    )
    (net (code "246") (name "unconnected-(U15-DCD#-Pad12)") (class "Default")
      (node (ref "U15") (pin "12") (pinfunction "DCD#_12") (pintype "power_in+no_connect"))
    )
    (net (code "247") (name "unconnected-(U15-DSR#-Pad10)") (class "Default")
      (node (ref "U15") (pin "10") (pinfunction "DSR#_10") (pintype "power_in+no_connect"))
    )
    (net (code "248") (name "unconnected-(U15-R232-Pad15)") (class "Default")
      (node (ref "U15") (pin "15") (pinfunction "R232_15") (pintype "power_in+no_connect"))
    )
    (net (code "249") (name "unconnected-(U15-RI#-Pad11)") (class "Default")
      (node (ref "U15") (pin "11") (pinfunction "RI#_11") (pintype "power_in+no_connect"))
    )
    (net (code "250") (name "unconnected-(U19-DRX-Pad1)") (class "Default")
      (node (ref "U19") (pin "1") (pinfunction "DRX_1") (pintype "passive"))
    )
    (net (code "251") (name "unconnected-(U19-DTX-Pad2)") (class "Default")
      (node (ref "U19") (pin "2") (pinfunction "DTX_2") (pintype "passive"))
    )
    (net (code "252") (name "unconnected-(U19-RI_E-Pad3)") (class "Default")
      (node (ref "U19") (pin "3") (pinfunction "RI_E_3") (pintype "passive"))
    )
    (net (code "253") (name "unconnected-(U20-NC-Pad1)") (class "Default")
      (node (ref "U20") (pin "1") (pinfunction "NC_1") (pintype "passive+no_connect"))
    )
    (net (code "254") (name "unconnected-(U20-NC-Pad4)") (class "Default")
      (node (ref "U20") (pin "4") (pinfunction "NC_4") (pintype "passive+no_connect"))
    )
    (net (code "255") (name "unconnected-(U21-NC-Pad1)") (class "Default")
      (node (ref "U21") (pin "1") (pinfunction "NC_1") (pintype "passive+no_connect"))
    )
    (net (code "256") (name "unconnected-(U21-NC-Pad4)") (class "Default")
      (node (ref "U21") (pin "4") (pinfunction "NC_4") (pintype "passive+no_connect"))
    )
    (net (code "257") (name "unconnected-(U22-NC-Pad1)") (class "Default")
      (node (ref "U22") (pin "1") (pinfunction "NC_1") (pintype "passive+no_connect"))
    )
    (net (code "258") (name "unconnected-(U22-NC-Pad4)") (class "Default")
      (node (ref "U22") (pin "4") (pinfunction "NC_4") (pintype "passive+no_connect"))
    )
    (net (code "259") (name "unconnected-(U23-NC-Pad1)") (class "Default")
      (node (ref "U23") (pin "1") (pinfunction "NC_1") (pintype "passive+no_connect"))
    )
    (net (code "260") (name "unconnected-(U23-NC-Pad4)") (class "Default")
      (node (ref "U23") (pin "4") (pinfunction "NC_4") (pintype "passive+no_connect"))
    )
    (net (code "261") (name "unconnected-(U24-NC-Pad5)") (class "Default")
      (node (ref "U24") (pin "5") (pinfunction "NC_5") (pintype "passive+no_connect"))
    )
    (net (code "262") (name "unconnected-(U24-NC-Pad6)") (class "Default")
      (node (ref "U24") (pin "6") (pinfunction "NC_6") (pintype "passive+no_connect"))
    )
    (net (code "263") (name "unconnected-(U26-NC-Pad7)") (class "Default")
      (node (ref "U26") (pin "7") (pinfunction "NC_7") (pintype "passive+no_connect"))
    )
    (net (code "264") (name "unconnected-(U26-NC-Pad8)") (class "Default")
      (node (ref "U26") (pin "8") (pinfunction "NC_8") (pintype "passive+no_connect"))
    )
    (net (code "265") (name "unconnected-(U26-TP-Pad1)") (class "Default")
      (node (ref "U26") (pin "1") (pinfunction "TP_1") (pintype "passive+no_connect"))
    )
    (net (code "266") (name "unconnected-(U26-TP-Pad5)") (class "Default")
      (node (ref "U26") (pin "5") (pinfunction "TP_5") (pintype "passive+no_connect"))
    )
    (net (code "267") (name "unconnected-(USB1-NC-Pad4)") (class "Default")
      (node (ref "USB1") (pin "4") (pinfunction "NC_4") (pintype "power_in+no_connect"))
    )
  )
)
